# MEMORY.net
KiCad netlist of a schematic drawn in Altium Designer
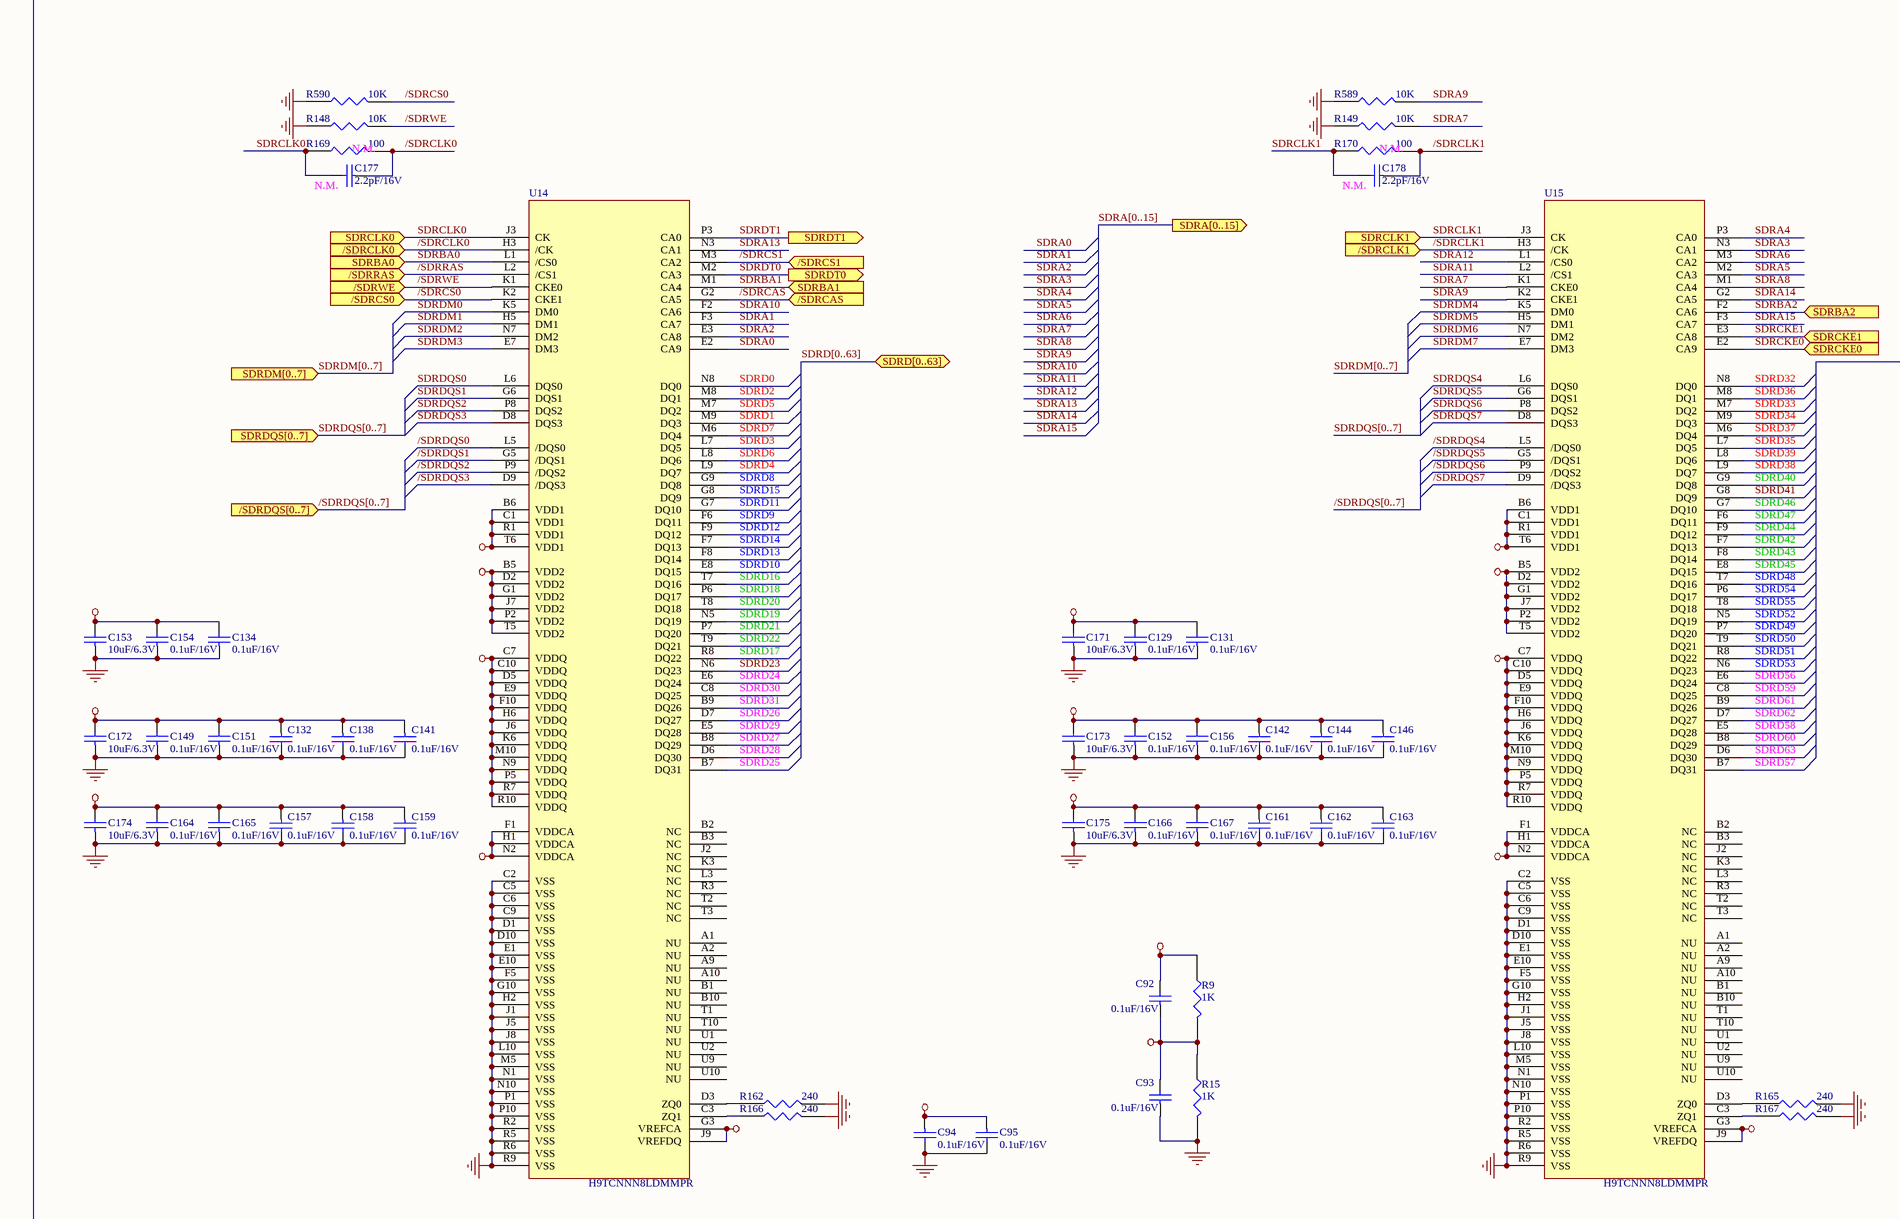
[diagram p0: MEMORY.schdoc, top left]
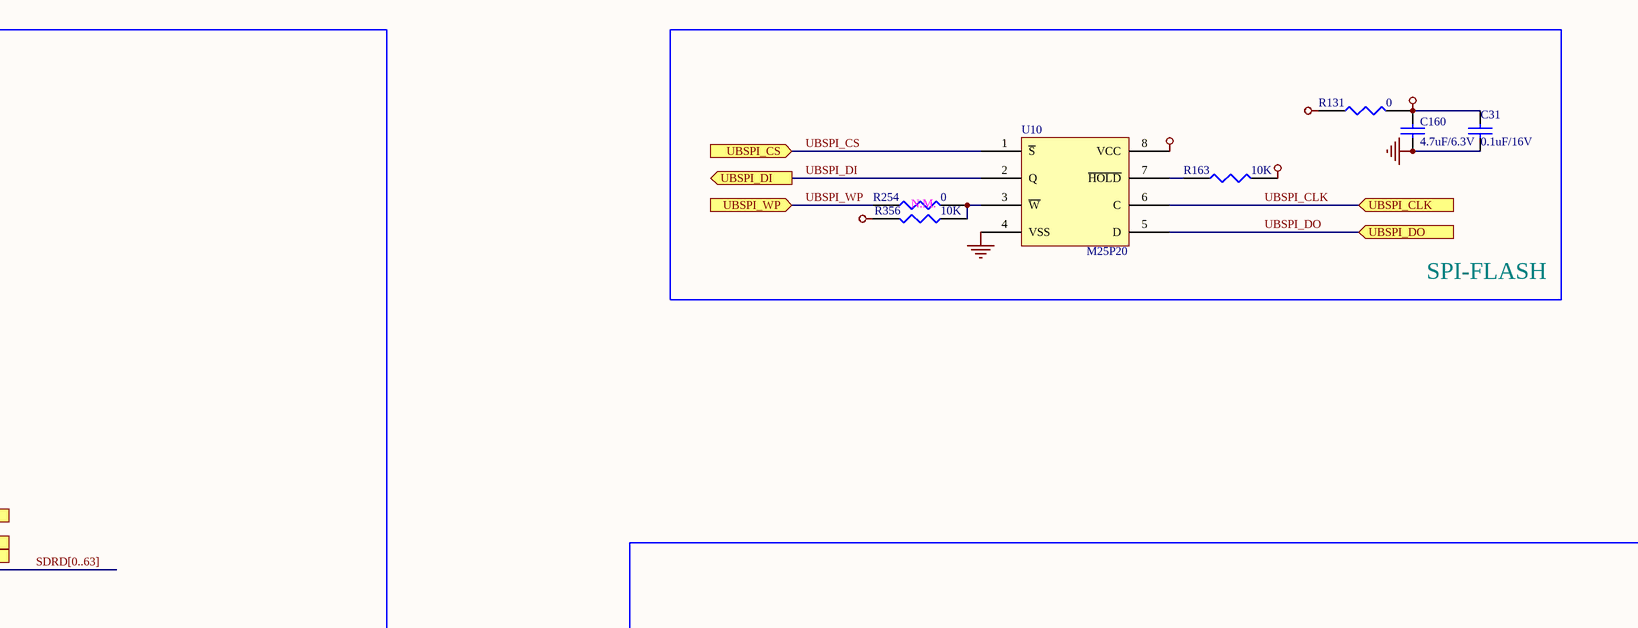
[diagram p1: MEMORY.schdoc, top right]
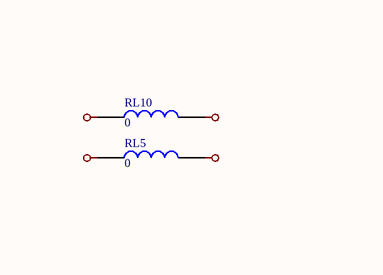
[diagram p2: MEMORY.schdoc, bottom left]
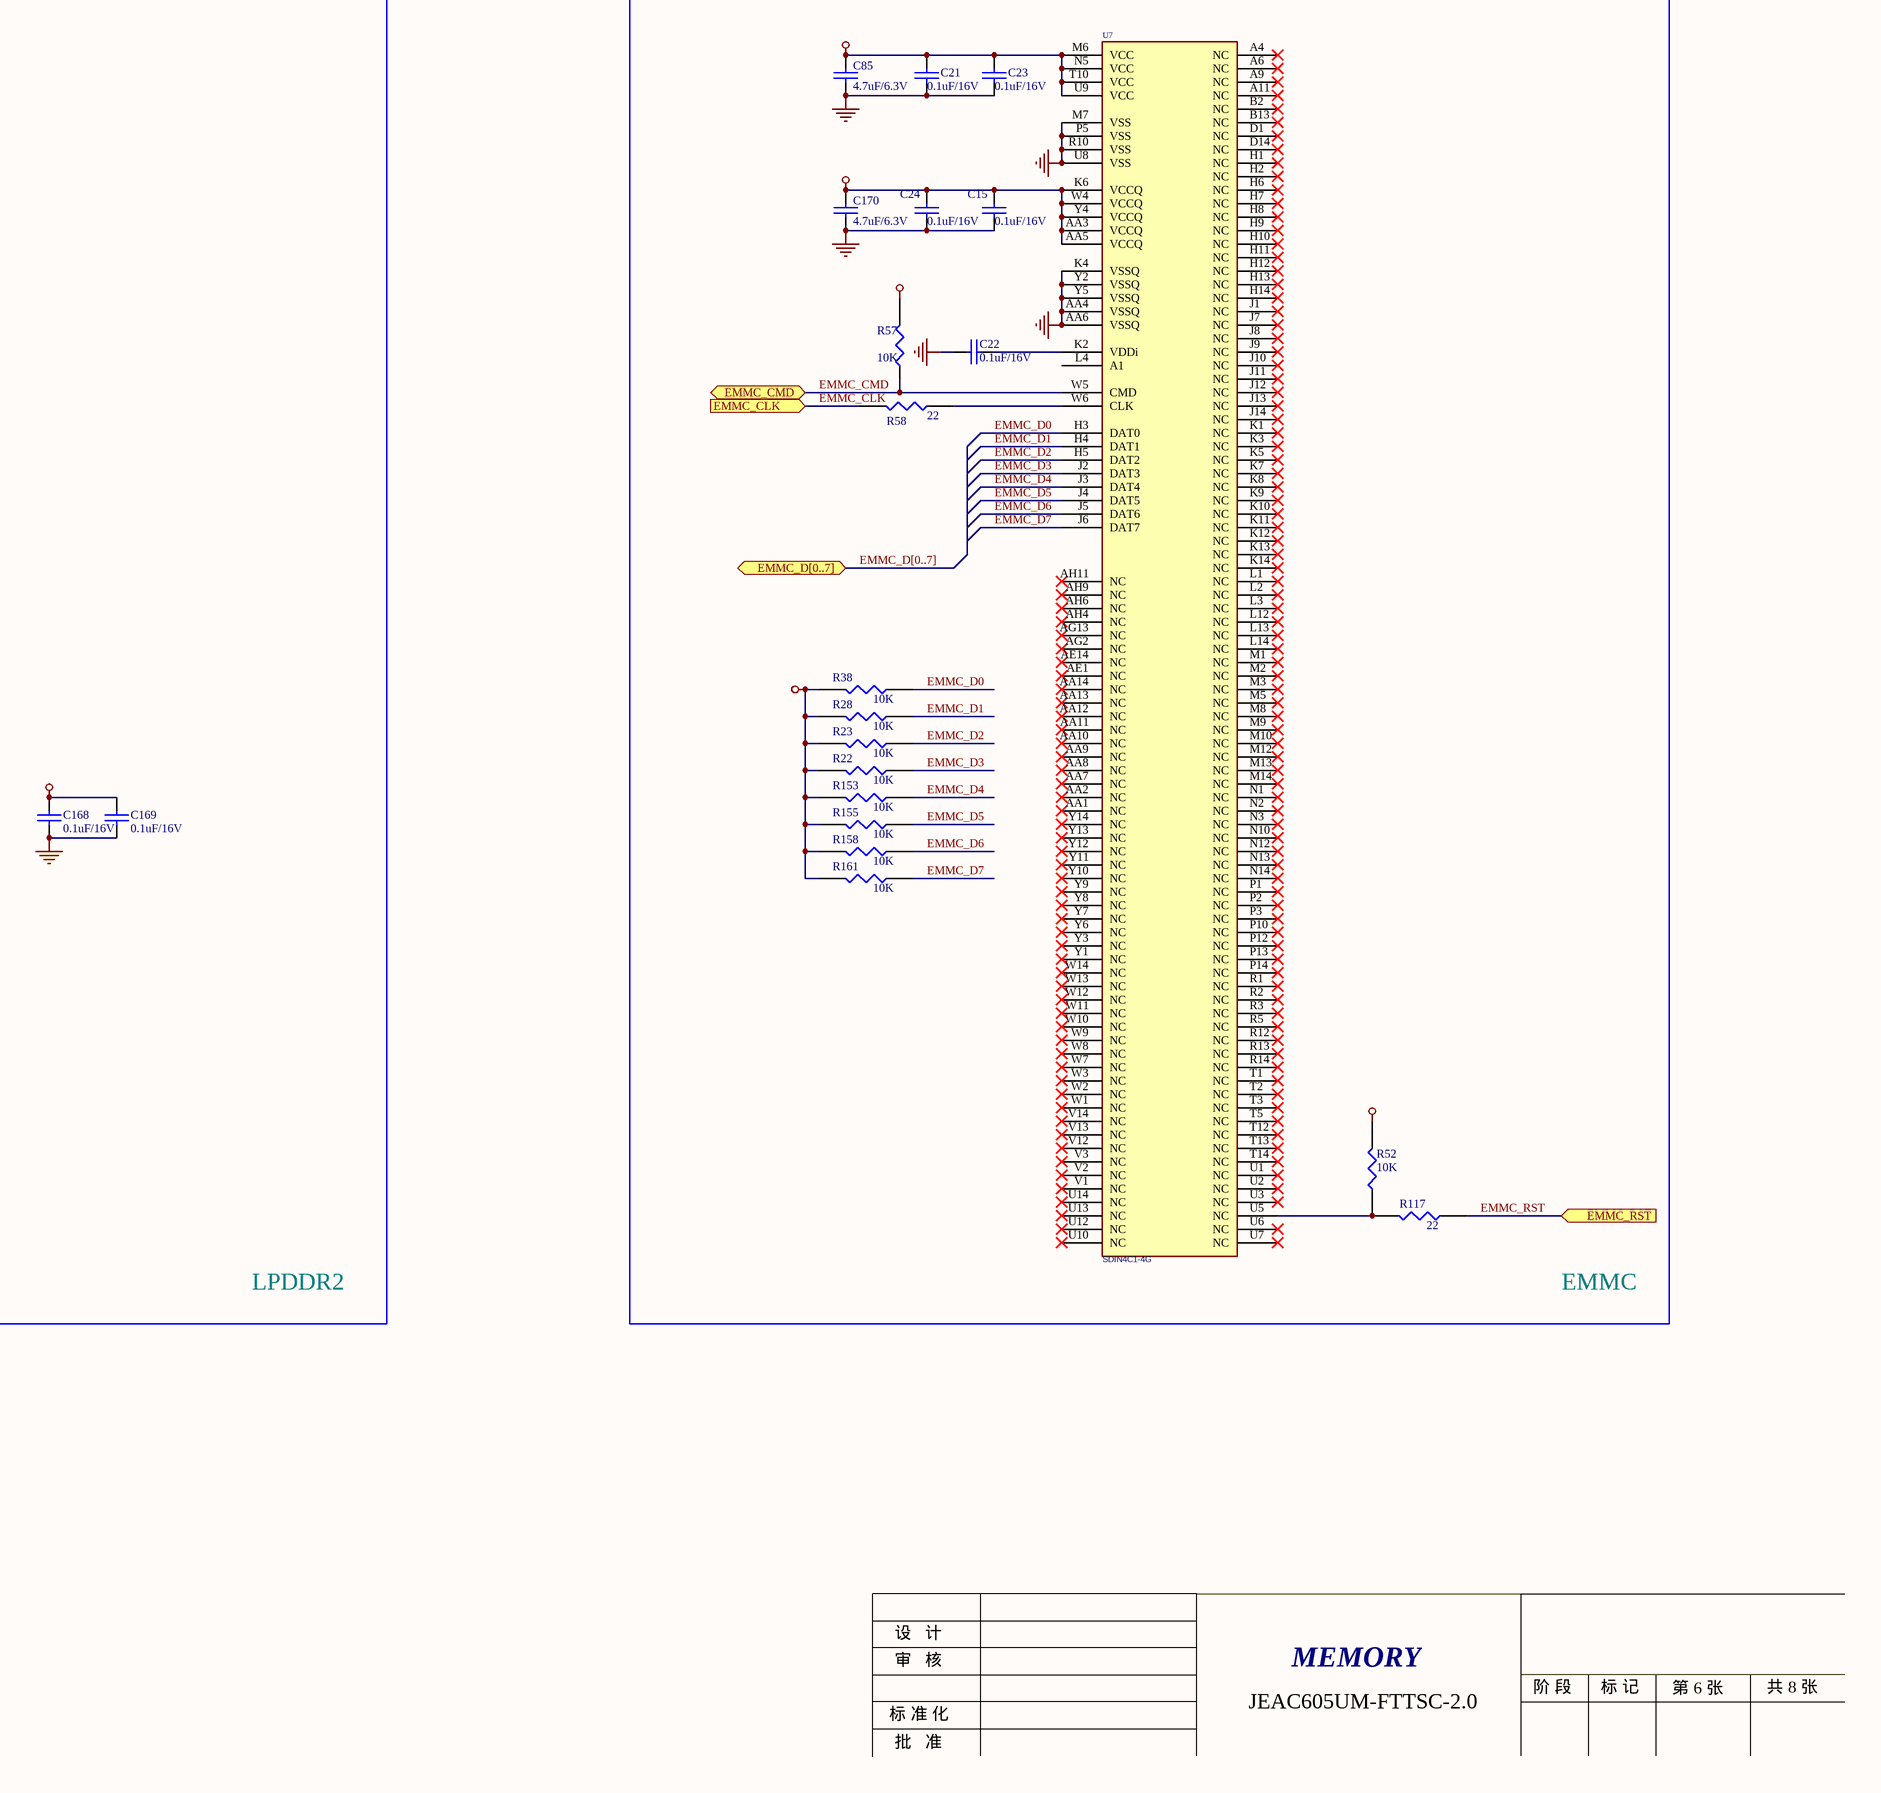
[diagram p3: MEMORY.schdoc, bottom right]

(export (version "E")
  (design (tool "Eeschema 10.0.6"))
  (components
    (comp (ref "C15")
      (value "0.1uF/16V")
      (footprint "C0402")
      (description "Capacitor")
      (libsource (lib "*") (part "CAP"))
    )
    (comp (ref "C21")
      (value "0.1uF/16V")
      (footprint "C0402")
      (description "Capacitor")
      (libsource (lib "*") (part "CAP"))
    )
    (comp (ref "C22")
      (value "0.1uF/16V")
      (footprint "C0402")
      (description "Capacitor")
      (libsource (lib "*") (part "CAP"))
    )
    (comp (ref "C23")
      (value "0.1uF/16V")
      (footprint "C0402")
      (description "Capacitor")
      (libsource (lib "*") (part "CAP"))
    )
    (comp (ref "C24")
      (value "0.1uF/16V")
      (footprint "C0402")
      (description "Capacitor")
      (libsource (lib "*") (part "CAP"))
    )
    (comp (ref "C31")
      (value "0.1uF/16V")
      (footprint "C0402")
      (description "Capacitor")
      (libsource (lib "*") (part "CAP"))
    )
    (comp (ref "C85")
      (value "4.7uF/6.3V")
      (footprint "C0603")
      (description "Capacitor")
      (libsource (lib "*") (part "CAP"))
    )
    (comp (ref "C92")
      (value "0.1uF/16V")
      (footprint "C0402")
      (description "Capacitor")
      (libsource (lib "*") (part "CAP"))
    )
    (comp (ref "C93")
      (value "0.1uF/16V")
      (footprint "C0402")
      (description "Capacitor")
      (libsource (lib "*") (part "CAP"))
    )
    (comp (ref "C94")
      (value "0.1uF/16V")
      (footprint "C0402")
      (description "Capacitor")
      (libsource (lib "*") (part "CAP"))
    )
    (comp (ref "C95")
      (value "0.1uF/16V")
      (footprint "C0402")
      (description "Capacitor")
      (libsource (lib "*") (part "CAP"))
    )
    (comp (ref "C129")
      (value "0.1uF/16V")
      (footprint "C0402")
      (description "Capacitor")
      (libsource (lib "*") (part "CAP"))
    )
    (comp (ref "C131")
      (value "0.1uF/16V")
      (footprint "C0402")
      (description "Capacitor")
      (libsource (lib "*") (part "CAP"))
    )
    (comp (ref "C132")
      (value "0.1uF/16V")
      (footprint "C0402")
      (description "Capacitor")
      (libsource (lib "*") (part "CAP"))
    )
    (comp (ref "C134")
      (value "0.1uF/16V")
      (footprint "C0402")
      (description "Capacitor")
      (libsource (lib "*") (part "CAP"))
    )
    (comp (ref "C138")
      (value "0.1uF/16V")
      (footprint "C0402")
      (description "Capacitor")
      (libsource (lib "*") (part "CAP"))
    )
    (comp (ref "C141")
      (value "0.1uF/16V")
      (footprint "C0402")
      (description "Capacitor")
      (libsource (lib "*") (part "CAP"))
    )
    (comp (ref "C142")
      (value "0.1uF/16V")
      (footprint "C0402")
      (description "Capacitor")
      (libsource (lib "*") (part "CAP"))
    )
    (comp (ref "C144")
      (value "0.1uF/16V")
      (footprint "C0402")
      (description "Capacitor")
      (libsource (lib "*") (part "CAP"))
    )
    (comp (ref "C146")
      (value "0.1uF/16V")
      (footprint "C0402")
      (description "Capacitor")
      (libsource (lib "*") (part "CAP"))
    )
    (comp (ref "C149")
      (value "0.1uF/16V")
      (footprint "C0402")
      (description "Capacitor")
      (libsource (lib "*") (part "CAP"))
    )
    (comp (ref "C151")
      (value "0.1uF/16V")
      (footprint "C0402")
      (description "Capacitor")
      (libsource (lib "*") (part "CAP"))
    )
    (comp (ref "C152")
      (value "0.1uF/16V")
      (footprint "C0402")
      (description "Capacitor")
      (libsource (lib "*") (part "CAP"))
    )
    (comp (ref "C153")
      (value "10uF/6.3V")
      (footprint "C0603")
      (description "Capacitor")
      (libsource (lib "*") (part "CAP"))
    )
    (comp (ref "C154")
      (value "0.1uF/16V")
      (footprint "C0402")
      (description "Capacitor")
      (libsource (lib "*") (part "CAP"))
    )
    (comp (ref "C156")
      (value "0.1uF/16V")
      (footprint "C0402")
      (description "Capacitor")
      (libsource (lib "*") (part "CAP"))
    )
    (comp (ref "C157")
      (value "0.1uF/16V")
      (footprint "C0402")
      (description "Capacitor")
      (libsource (lib "*") (part "CAP"))
    )
    (comp (ref "C158")
      (value "0.1uF/16V")
      (footprint "C0402")
      (description "Capacitor")
      (libsource (lib "*") (part "CAP"))
    )
    (comp (ref "C159")
      (value "0.1uF/16V")
      (footprint "C0402")
      (description "Capacitor")
      (libsource (lib "*") (part "CAP"))
    )
    (comp (ref "C160")
      (value "4.7uF/6.3V")
      (footprint "C0603")
      (description "Capacitor")
      (libsource (lib "*") (part "CAP"))
    )
    (comp (ref "C161")
      (value "0.1uF/16V")
      (footprint "C0402")
      (description "Capacitor")
      (libsource (lib "*") (part "CAP"))
    )
    (comp (ref "C162")
      (value "0.1uF/16V")
      (footprint "C0402")
      (description "Capacitor")
      (libsource (lib "*") (part "CAP"))
    )
    (comp (ref "C163")
      (value "0.1uF/16V")
      (footprint "C0402")
      (description "Capacitor")
      (libsource (lib "*") (part "CAP"))
    )
    (comp (ref "C164")
      (value "0.1uF/16V")
      (footprint "C0402")
      (description "Capacitor")
      (libsource (lib "*") (part "CAP"))
    )
    (comp (ref "C165")
      (value "0.1uF/16V")
      (footprint "C0402")
      (description "Capacitor")
      (libsource (lib "*") (part "CAP"))
    )
    (comp (ref "C166")
      (value "0.1uF/16V")
      (footprint "C0402")
      (description "Capacitor")
      (libsource (lib "*") (part "CAP"))
    )
    (comp (ref "C167")
      (value "0.1uF/16V")
      (footprint "C0402")
      (description "Capacitor")
      (libsource (lib "*") (part "CAP"))
    )
    (comp (ref "C168")
      (value "0.1uF/16V")
      (footprint "C0402")
      (description "Capacitor")
      (libsource (lib "*") (part "CAP"))
    )
    (comp (ref "C169")
      (value "0.1uF/16V")
      (footprint "C0402")
      (description "Capacitor")
      (libsource (lib "*") (part "CAP"))
    )
    (comp (ref "C170")
      (value "4.7uF/6.3V")
      (footprint "C0603")
      (description "Capacitor")
      (libsource (lib "*") (part "CAP"))
    )
    (comp (ref "C171")
      (value "10uF/6.3V")
      (footprint "C0603")
      (description "Capacitor")
      (libsource (lib "*") (part "CAP"))
    )
    (comp (ref "C172")
      (value "10uF/6.3V")
      (footprint "C0603")
      (description "Capacitor")
      (libsource (lib "*") (part "CAP"))
    )
    (comp (ref "C173")
      (value "10uF/6.3V")
      (footprint "C0603")
      (description "Capacitor")
      (libsource (lib "*") (part "CAP"))
    )
    (comp (ref "C174")
      (value "10uF/6.3V")
      (footprint "C0603")
      (description "Capacitor")
      (libsource (lib "*") (part "CAP"))
    )
    (comp (ref "C175")
      (value "10uF/6.3V")
      (footprint "C0603")
      (description "Capacitor")
      (libsource (lib "*") (part "CAP"))
    )
    (comp (ref "C177")
      (value "2.2pF/16V")
      (footprint "C0402")
      (description "Capacitor")
      (libsource (lib "*") (part "CAP"))
    )
    (comp (ref "C178")
      (value "2.2pF/16V")
      (footprint "C0402")
      (description "Capacitor")
      (libsource (lib "*") (part "CAP"))
    )
    (comp (ref "R9") (value "1K") (footprint "R0402") (libsource (lib "*") (part "RES1")))
    (comp (ref "R15") (value "1K") (footprint "R0402") (libsource (lib "*") (part "RES1")))
    (comp (ref "R22") (value "10K") (footprint "R0402") (libsource (lib "*") (part "RES1")))
    (comp (ref "R23") (value "10K") (footprint "R0402") (libsource (lib "*") (part "RES1")))
    (comp (ref "R28") (value "10K") (footprint "R0402") (libsource (lib "*") (part "RES1")))
    (comp (ref "R38") (value "10K") (footprint "R0402") (libsource (lib "*") (part "RES1")))
    (comp (ref "R52") (value "10K") (footprint "R0402") (libsource (lib "*") (part "RES1")))
    (comp (ref "R57") (value "10K") (footprint "R0402") (libsource (lib "*") (part "RES1")))
    (comp (ref "R58") (value "22") (footprint "R0402") (libsource (lib "*") (part "RES1")))
    (comp (ref "R117") (value "22") (footprint "R0402") (libsource (lib "*") (part "RES1")))
    (comp (ref "R131") (value "0") (footprint "R0402") (libsource (lib "*") (part "RES1")))
    (comp (ref "R148") (value "10K") (footprint "R0402") (libsource (lib "*") (part "RES1")))
    (comp (ref "R149") (value "10K") (footprint "R0402") (libsource (lib "*") (part "RES1")))
    (comp (ref "R153") (value "10K") (footprint "R0402") (libsource (lib "*") (part "RES1")))
    (comp (ref "R155") (value "10K") (footprint "R0402") (libsource (lib "*") (part "RES1")))
    (comp (ref "R158") (value "10K") (footprint "R0402") (libsource (lib "*") (part "RES1")))
    (comp (ref "R161") (value "10K") (footprint "R0402") (libsource (lib "*") (part "RES1")))
    (comp (ref "R162") (value "240") (footprint "R0402") (libsource (lib "*") (part "RES1")))
    (comp (ref "R163") (value "10K") (footprint "R0402") (libsource (lib "*") (part "RES1")))
    (comp (ref "R165") (value "240") (footprint "R0402") (libsource (lib "*") (part "RES1")))
    (comp (ref "R166") (value "240") (footprint "R0402") (libsource (lib "*") (part "RES1")))
    (comp (ref "R167") (value "240") (footprint "R0402") (libsource (lib "*") (part "RES1")))
    (comp (ref "R169") (value "100") (footprint "R0402") (libsource (lib "*") (part "RES1")))
    (comp (ref "R170") (value "100") (footprint "R0402") (libsource (lib "*") (part "RES1")))
    (comp (ref "R254") (value "0") (footprint "R0402") (libsource (lib "*") (part "RES1")))
    (comp (ref "R356") (value "10K") (footprint "R0402") (libsource (lib "*") (part "RES1")))
    (comp (ref "R589") (value "10K") (footprint "R0402") (libsource (lib "*") (part "RES1")))
    (comp (ref "R590") (value "10K") (footprint "R0402") (libsource (lib "*") (part "RES1")))
    (comp (ref "RL5") (value "0") (footprint "L0603") (libsource (lib "*") (part "INDUCTOR")))
    (comp (ref "RL10") (value "0") (footprint "L0603") (libsource (lib "*") (part "INDUCTOR")))
    (comp (ref "U7") (value "SDIN4C1-4G") (libsource (lib "SOM3621") (part "SDIN3C2-16G")))
    (comp (ref "U10") (value "M25P20") (footprint "U-SO-8-1_27") (libsource (lib "*") (part "A25L80P")))
    (comp (ref "U14")
      (value "H9TCNNN8LDMMPR")
      (footprint "U-FBGA-134-0_65")
      (libsource (lib "*") (part "EDB8132B2MA"))
    )
    (comp (ref "U15")
      (value "H9TCNNN8LDMMPR")
      (footprint "U-FBGA-134-0_65")
      (libsource (lib "*") (part "EDB8132B2MA"))
    )
  )
  (nets
    (net (code "9") (name "/EMMC_CLK") (class "Default")
      (node (ref "R58") (pin "2") (pinfunction "2_2") (pintype "passive"))
    )
    (net (code "10") (name "/EMMC_CMD") (class "Default")
      (node (ref "R57") (pin "1") (pinfunction "1_1") (pintype "passive"))
      (node (ref "U7") (pin "W5") (pinfunction "CMD_W5") (pintype "passive"))
    )
    (net (code "11") (name "/EMMC_D0") (class "Default")
      (node (ref "R38") (pin "1") (pinfunction "1_1") (pintype "passive"))
      (node (ref "U7") (pin "H3") (pinfunction "DAT0_H3") (pintype "passive"))
    )
    (net (code "12") (name "/EMMC_D1") (class "Default")
      (node (ref "R28") (pin "1") (pinfunction "1_1") (pintype "passive"))
      (node (ref "U7") (pin "H4") (pinfunction "DAT1_H4") (pintype "passive"))
    )
    (net (code "13") (name "/EMMC_D2") (class "Default")
      (node (ref "R23") (pin "1") (pinfunction "1_1") (pintype "passive"))
      (node (ref "U7") (pin "H5") (pinfunction "DAT2_H5") (pintype "passive"))
    )
    (net (code "14") (name "/EMMC_D3") (class "Default")
      (node (ref "R22") (pin "1") (pinfunction "1_1") (pintype "passive"))
      (node (ref "U7") (pin "J2") (pinfunction "DAT3_J2") (pintype "passive"))
    )
    (net (code "15") (name "/EMMC_D4") (class "Default")
      (node (ref "R153") (pin "1") (pinfunction "1_1") (pintype "passive"))
      (node (ref "U7") (pin "J3") (pinfunction "DAT4_J3") (pintype "passive"))
    )
    (net (code "16") (name "/EMMC_D5") (class "Default")
      (node (ref "R155") (pin "1") (pinfunction "1_1") (pintype "passive"))
      (node (ref "U7") (pin "J4") (pinfunction "DAT5_J4") (pintype "passive"))
    )
    (net (code "17") (name "/EMMC_D6") (class "Default")
      (node (ref "R158") (pin "1") (pinfunction "1_1") (pintype "passive"))
      (node (ref "U7") (pin "J5") (pinfunction "DAT6_J5") (pintype "passive"))
    )
    (net (code "18") (name "/EMMC_D7") (class "Default")
      (node (ref "R161") (pin "1") (pinfunction "1_1") (pintype "passive"))
      (node (ref "U7") (pin "J6") (pinfunction "DAT7_J6") (pintype "passive"))
    )
    (net (code "20") (name "/EMMC_RST") (class "Default")
      (node (ref "R117") (pin "1") (pinfunction "1_1") (pintype "passive"))
    )
    (net (code "21") (name "/SDRA0") (class "Default")
      (node (ref "U14") (pin "E2") (pinfunction "CA9_E2") (pintype "passive"))
    )
    (net (code "22") (name "/SDRA1") (class "Default")
      (node (ref "U14") (pin "F3") (pinfunction "CA7_F3") (pintype "passive"))
    )
    (net (code "23") (name "/SDRA2") (class "Default")
      (node (ref "U14") (pin "E3") (pinfunction "CA8_E3") (pintype "passive"))
    )
    (net (code "24") (name "/SDRA3") (class "Default")
      (node (ref "U15") (pin "N3") (pinfunction "CA1_N3") (pintype "passive"))
    )
    (net (code "25") (name "/SDRA4") (class "Default")
      (node (ref "U15") (pin "P3") (pinfunction "CA0_P3") (pintype "passive"))
    )
    (net (code "26") (name "/SDRA5") (class "Default")
      (node (ref "U15") (pin "M2") (pinfunction "CA3_M2") (pintype "passive"))
    )
    (net (code "27") (name "/SDRA6") (class "Default")
      (node (ref "U15") (pin "M3") (pinfunction "CA2_M3") (pintype "passive"))
    )
    (net (code "28") (name "/SDRA7") (class "Default")
      (node (ref "R149") (pin "2") (pinfunction "2_2") (pintype "passive"))
      (node (ref "U15") (pin "K1") (pinfunction "CKE0_K1") (pintype "passive"))
    )
    (net (code "29") (name "/SDRA8") (class "Default")
      (node (ref "U15") (pin "M1") (pinfunction "CA4_M1") (pintype "passive"))
    )
    (net (code "30") (name "/SDRA9") (class "Default")
      (node (ref "R589") (pin "2") (pinfunction "2_2") (pintype "passive"))
      (node (ref "U15") (pin "K2") (pinfunction "CKE1_K2") (pintype "passive"))
    )
    (net (code "31") (name "/SDRA10") (class "Default")
      (node (ref "U14") (pin "F2") (pinfunction "CA6_F2") (pintype "passive"))
    )
    (net (code "32") (name "/SDRA11") (class "Default")
      (node (ref "U15") (pin "L2") (pinfunction "/CS1_L2") (pintype "passive"))
    )
    (net (code "33") (name "/SDRA12") (class "Default")
      (node (ref "U15") (pin "L1") (pinfunction "/CS0_L1") (pintype "passive"))
    )
    (net (code "34") (name "/SDRA13") (class "Default")
      (node (ref "U14") (pin "N3") (pinfunction "CA1_N3") (pintype "passive"))
    )
    (net (code "35") (name "/SDRA14") (class "Default")
      (node (ref "U15") (pin "G2") (pinfunction "CA5_G2") (pintype "passive"))
    )
    (net (code "36") (name "/SDRA15") (class "Default")
      (node (ref "U15") (pin "F3") (pinfunction "CA7_F3") (pintype "passive"))
    )
    (net (code "38") (name "/SDRBA0") (class "Default")
      (node (ref "U14") (pin "L1") (pinfunction "/CS0_L1") (pintype "passive"))
    )
    (net (code "39") (name "/SDRBA1") (class "Default")
      (node (ref "U14") (pin "M1") (pinfunction "CA4_M1") (pintype "passive"))
    )
    (net (code "40") (name "/SDRBA2") (class "Default")
      (node (ref "U15") (pin "F2") (pinfunction "CA6_F2") (pintype "passive"))
    )
    (net (code "41") (name "/SDRCKE0") (class "Default")
      (node (ref "U15") (pin "E2") (pinfunction "CA9_E2") (pintype "passive"))
    )
    (net (code "42") (name "/SDRCKE1") (class "Default")
      (node (ref "U15") (pin "E3") (pinfunction "CA8_E3") (pintype "passive"))
    )
    (net (code "43") (name "/SDRCLK0") (class "Default")
      (node (ref "C177") (pin "2") (pinfunction "2_2") (pintype "passive"))
      (node (ref "R169") (pin "1") (pinfunction "1_1") (pintype "passive"))
      (node (ref "U14") (pin "J3") (pinfunction "CK_J3") (pintype "passive"))
    )
    (net (code "44") (name "/SDRCLK1") (class "Default")
      (node (ref "C178") (pin "2") (pinfunction "2_2") (pintype "passive"))
      (node (ref "R170") (pin "1") (pinfunction "1_1") (pintype "passive"))
      (node (ref "U15") (pin "J3") (pinfunction "CK_J3") (pintype "passive"))
    )
    (net (code "45") (name "/SDRD0") (class "Default")
      (node (ref "U14") (pin "N8") (pinfunction "DQ0_N8") (pintype "passive"))
    )
    (net (code "46") (name "/SDRD1") (class "Default")
      (node (ref "U14") (pin "M9") (pinfunction "DQ3_M9") (pintype "passive"))
    )
    (net (code "47") (name "/SDRD2") (class "Default")
      (node (ref "U14") (pin "M8") (pinfunction "DQ1_M8") (pintype "passive"))
    )
    (net (code "48") (name "/SDRD3") (class "Default")
      (node (ref "U14") (pin "L7") (pinfunction "DQ5_L7") (pintype "passive"))
    )
    (net (code "49") (name "/SDRD4") (class "Default")
      (node (ref "U14") (pin "L9") (pinfunction "DQ7_L9") (pintype "passive"))
    )
    (net (code "50") (name "/SDRD5") (class "Default")
      (node (ref "U14") (pin "M7") (pinfunction "DQ2_M7") (pintype "passive"))
    )
    (net (code "51") (name "/SDRD6") (class "Default")
      (node (ref "U14") (pin "L8") (pinfunction "DQ6_L8") (pintype "passive"))
    )
    (net (code "52") (name "/SDRD7") (class "Default")
      (node (ref "U14") (pin "M6") (pinfunction "DQ4_M6") (pintype "passive"))
    )
    (net (code "53") (name "/SDRD8") (class "Default")
      (node (ref "U14") (pin "G9") (pinfunction "DQ8_G9") (pintype "passive"))
    )
    (net (code "54") (name "/SDRD9") (class "Default")
      (node (ref "U14") (pin "F6") (pinfunction "DQ11_F6") (pintype "passive"))
    )
    (net (code "55") (name "/SDRD10") (class "Default")
      (node (ref "U14") (pin "E8") (pinfunction "DQ15_E8") (pintype "passive"))
    )
    (net (code "56") (name "/SDRD11") (class "Default")
      (node (ref "U14") (pin "G7") (pinfunction "DQ10_G7") (pintype "passive"))
    )
    (net (code "57") (name "/SDRD12") (class "Default")
      (node (ref "U14") (pin "F9") (pinfunction "DQ12_F9") (pintype "passive"))
    )
    (net (code "58") (name "/SDRD13") (class "Default")
      (node (ref "U14") (pin "F8") (pinfunction "DQ14_F8") (pintype "passive"))
    )
    (net (code "59") (name "/SDRD14") (class "Default")
      (node (ref "U14") (pin "F7") (pinfunction "DQ13_F7") (pintype "passive"))
    )
    (net (code "60") (name "/SDRD15") (class "Default")
      (node (ref "U14") (pin "G8") (pinfunction "DQ9_G8") (pintype "passive"))
    )
    (net (code "61") (name "/SDRD16") (class "Default")
      (node (ref "U14") (pin "T7") (pinfunction "DQ16_T7") (pintype "passive"))
    )
    (net (code "62") (name "/SDRD17") (class "Default")
      (node (ref "U14") (pin "R8") (pinfunction "DQ22_R8") (pintype "passive"))
    )
    (net (code "63") (name "/SDRD18") (class "Default")
      (node (ref "U14") (pin "P6") (pinfunction "DQ17_P6") (pintype "passive"))
    )
    (net (code "64") (name "/SDRD19") (class "Default")
      (node (ref "U14") (pin "N5") (pinfunction "DQ19_N5") (pintype "passive"))
    )
    (net (code "65") (name "/SDRD20") (class "Default")
      (node (ref "U14") (pin "T8") (pinfunction "DQ18_T8") (pintype "passive"))
    )
    (net (code "66") (name "/SDRD21") (class "Default")
      (node (ref "U14") (pin "P7") (pinfunction "DQ20_P7") (pintype "passive"))
    )
    (net (code "67") (name "/SDRD22") (class "Default")
      (node (ref "U14") (pin "T9") (pinfunction "DQ21_T9") (pintype "passive"))
    )
    (net (code "68") (name "/SDRD23") (class "Default")
      (node (ref "U14") (pin "N6") (pinfunction "DQ23_N6") (pintype "passive"))
    )
    (net (code "69") (name "/SDRD24") (class "Default")
      (node (ref "U14") (pin "E6") (pinfunction "DQ24_E6") (pintype "passive"))
    )
    (net (code "70") (name "/SDRD25") (class "Default")
      (node (ref "U14") (pin "B7") (pinfunction "DQ31_B7") (pintype "passive"))
    )
    (net (code "71") (name "/SDRD26") (class "Default")
      (node (ref "U14") (pin "D7") (pinfunction "DQ27_D7") (pintype "passive"))
    )
    (net (code "72") (name "/SDRD27") (class "Default")
      (node (ref "U14") (pin "B8") (pinfunction "DQ29_B8") (pintype "passive"))
    )
    (net (code "73") (name "/SDRD28") (class "Default")
      (node (ref "U14") (pin "D6") (pinfunction "DQ30_D6") (pintype "passive"))
    )
    (net (code "74") (name "/SDRD29") (class "Default")
      (node (ref "U14") (pin "E5") (pinfunction "DQ28_E5") (pintype "passive"))
    )
    (net (code "75") (name "/SDRD30") (class "Default")
      (node (ref "U14") (pin "C8") (pinfunction "DQ25_C8") (pintype "passive"))
    )
    (net (code "76") (name "/SDRD31") (class "Default")
      (node (ref "U14") (pin "B9") (pinfunction "DQ26_B9") (pintype "passive"))
    )
    (net (code "77") (name "/SDRD32") (class "Default")
      (node (ref "U15") (pin "N8") (pinfunction "DQ0_N8") (pintype "passive"))
    )
    (net (code "78") (name "/SDRD33") (class "Default")
      (node (ref "U15") (pin "M7") (pinfunction "DQ2_M7") (pintype "passive"))
    )
    (net (code "79") (name "/SDRD34") (class "Default")
      (node (ref "U15") (pin "M9") (pinfunction "DQ3_M9") (pintype "passive"))
    )
    (net (code "80") (name "/SDRD35") (class "Default")
      (node (ref "U15") (pin "L7") (pinfunction "DQ5_L7") (pintype "passive"))
    )
    (net (code "81") (name "/SDRD36") (class "Default")
      (node (ref "U15") (pin "M8") (pinfunction "DQ1_M8") (pintype "passive"))
    )
    (net (code "82") (name "/SDRD37") (class "Default")
      (node (ref "U15") (pin "M6") (pinfunction "DQ4_M6") (pintype "passive"))
    )
    (net (code "83") (name "/SDRD38") (class "Default")
      (node (ref "U15") (pin "L9") (pinfunction "DQ7_L9") (pintype "passive"))
    )
    (net (code "84") (name "/SDRD39") (class "Default")
      (node (ref "U15") (pin "L8") (pinfunction "DQ6_L8") (pintype "passive"))
    )
    (net (code "85") (name "/SDRD40") (class "Default")
      (node (ref "U15") (pin "G9") (pinfunction "DQ8_G9") (pintype "passive"))
    )
    (net (code "86") (name "/SDRD41") (class "Default")
      (node (ref "U15") (pin "G8") (pinfunction "DQ9_G8") (pintype "passive"))
    )
    (net (code "87") (name "/SDRD42") (class "Default")
      (node (ref "U15") (pin "F7") (pinfunction "DQ13_F7") (pintype "passive"))
    )
    (net (code "88") (name "/SDRD43") (class "Default")
      (node (ref "U15") (pin "F8") (pinfunction "DQ14_F8") (pintype "passive"))
    )
    (net (code "89") (name "/SDRD44") (class "Default")
      (node (ref "U15") (pin "F9") (pinfunction "DQ12_F9") (pintype "passive"))
    )
    (net (code "90") (name "/SDRD45") (class "Default")
      (node (ref "U15") (pin "E8") (pinfunction "DQ15_E8") (pintype "passive"))
    )
    (net (code "91") (name "/SDRD46") (class "Default")
      (node (ref "U15") (pin "G7") (pinfunction "DQ10_G7") (pintype "passive"))
    )
    (net (code "92") (name "/SDRD47") (class "Default")
      (node (ref "U15") (pin "F6") (pinfunction "DQ11_F6") (pintype "passive"))
    )
    (net (code "93") (name "/SDRD48") (class "Default")
      (node (ref "U15") (pin "T7") (pinfunction "DQ16_T7") (pintype "passive"))
    )
    (net (code "94") (name "/SDRD49") (class "Default")
      (node (ref "U15") (pin "P7") (pinfunction "DQ20_P7") (pintype "passive"))
    )
    (net (code "95") (name "/SDRD50") (class "Default")
      (node (ref "U15") (pin "T9") (pinfunction "DQ21_T9") (pintype "passive"))
    )
    (net (code "96") (name "/SDRD51") (class "Default")
      (node (ref "U15") (pin "R8") (pinfunction "DQ22_R8") (pintype "passive"))
    )
    (net (code "97") (name "/SDRD52") (class "Default")
      (node (ref "U15") (pin "N5") (pinfunction "DQ19_N5") (pintype "passive"))
    )
    (net (code "98") (name "/SDRD53") (class "Default")
      (node (ref "U15") (pin "N6") (pinfunction "DQ23_N6") (pintype "passive"))
    )
    (net (code "99") (name "/SDRD54") (class "Default")
      (node (ref "U15") (pin "P6") (pinfunction "DQ17_P6") (pintype "passive"))
    )
    (net (code "100") (name "/SDRD55") (class "Default")
      (node (ref "U15") (pin "T8") (pinfunction "DQ18_T8") (pintype "passive"))
    )
    (net (code "101") (name "/SDRD56") (class "Default")
      (node (ref "U15") (pin "E6") (pinfunction "DQ24_E6") (pintype "passive"))
    )
    (net (code "102") (name "/SDRD57") (class "Default")
      (node (ref "U15") (pin "B7") (pinfunction "DQ31_B7") (pintype "passive"))
    )
    (net (code "103") (name "/SDRD58") (class "Default")
      (node (ref "U15") (pin "E5") (pinfunction "DQ28_E5") (pintype "passive"))
    )
    (net (code "104") (name "/SDRD59") (class "Default")
      (node (ref "U15") (pin "C8") (pinfunction "DQ25_C8") (pintype "passive"))
    )
    (net (code "105") (name "/SDRD60") (class "Default")
      (node (ref "U15") (pin "B8") (pinfunction "DQ29_B8") (pintype "passive"))
    )
    (net (code "106") (name "/SDRD61") (class "Default")
      (node (ref "U15") (pin "B9") (pinfunction "DQ26_B9") (pintype "passive"))
    )
    (net (code "107") (name "/SDRD62") (class "Default")
      (node (ref "U15") (pin "D7") (pinfunction "DQ27_D7") (pintype "passive"))
    )
    (net (code "108") (name "/SDRD63") (class "Default")
      (node (ref "U15") (pin "D6") (pinfunction "DQ30_D6") (pintype "passive"))
    )
    (net (code "109") (name "/SDRDM0") (class "Default")
      (node (ref "U14") (pin "K5") (pinfunction "DM0_K5") (pintype "passive"))
    )
    (net (code "110") (name "/SDRDM1") (class "Default")
      (node (ref "U14") (pin "H5") (pinfunction "DM1_H5") (pintype "passive"))
    )
    (net (code "111") (name "/SDRDM2") (class "Default")
      (node (ref "U14") (pin "N7") (pinfunction "DM2_N7") (pintype "passive"))
    )
    (net (code "112") (name "/SDRDM3") (class "Default")
      (node (ref "U14") (pin "E7") (pinfunction "DM3_E7") (pintype "passive"))
    )
    (net (code "113") (name "/SDRDM4") (class "Default")
      (node (ref "U15") (pin "K5") (pinfunction "DM0_K5") (pintype "passive"))
    )
    (net (code "114") (name "/SDRDM5") (class "Default")
      (node (ref "U15") (pin "H5") (pinfunction "DM1_H5") (pintype "passive"))
    )
    (net (code "115") (name "/SDRDM6") (class "Default")
      (node (ref "U15") (pin "N7") (pinfunction "DM2_N7") (pintype "passive"))
    )
    (net (code "116") (name "/SDRDM7") (class "Default")
      (node (ref "U15") (pin "E7") (pinfunction "DM3_E7") (pintype "passive"))
    )
    (net (code "118") (name "/SDRDQS0") (class "Default")
      (node (ref "U14") (pin "L6") (pinfunction "DQS0_L6") (pintype "passive"))
    )
    (net (code "119") (name "/SDRDQS1") (class "Default")
      (node (ref "U14") (pin "G6") (pinfunction "DQS1_G6") (pintype "passive"))
    )
    (net (code "120") (name "/SDRDQS2") (class "Default")
      (node (ref "U14") (pin "P8") (pinfunction "DQS2_P8") (pintype "passive"))
    )
    (net (code "121") (name "/SDRDQS3") (class "Default")
      (node (ref "U14") (pin "D8") (pinfunction "DQS3_D8") (pintype "passive"))
    )
    (net (code "122") (name "/SDRDQS4") (class "Default")
      (node (ref "U15") (pin "L6") (pinfunction "DQS0_L6") (pintype "passive"))
    )
    (net (code "123") (name "/SDRDQS5") (class "Default")
      (node (ref "U15") (pin "G6") (pinfunction "DQS1_G6") (pintype "passive"))
    )
    (net (code "124") (name "/SDRDQS6") (class "Default")
      (node (ref "U15") (pin "P8") (pinfunction "DQS2_P8") (pintype "passive"))
    )
    (net (code "125") (name "/SDRDQS7") (class "Default")
      (node (ref "U15") (pin "D8") (pinfunction "DQS3_D8") (pintype "passive"))
    )
    (net (code "127") (name "/SDRDT0") (class "Default")
      (node (ref "U14") (pin "M2") (pinfunction "CA3_M2") (pintype "passive"))
    )
    (net (code "128") (name "/SDRDT1") (class "Default")
      (node (ref "U14") (pin "P3") (pinfunction "CA0_P3") (pintype "passive"))
    )
    (net (code "130") (name "/UBSPI_CLK") (class "Default")
      (node (ref "U10") (pin "6") (pinfunction "C_6") (pintype "passive"))
    )
    (net (code "131") (name "/UBSPI_CS") (class "Default")
      (node (ref "U10") (pin "1") (pinfunction "~{S}_1") (pintype "passive"))
    )
    (net (code "132") (name "/UBSPI_DI") (class "Default")
      (node (ref "U10") (pin "2") (pinfunction "Q_2") (pintype "passive"))
    )
    (net (code "133") (name "/UBSPI_DO") (class "Default")
      (node (ref "U10") (pin "5") (pinfunction "D_5") (pintype "passive"))
    )
    (net (code "134") (name "/UBSPI_WP") (class "Default")
      (node (ref "R254") (pin "1") (pinfunction "1_1") (pintype "passive"))
    )
    (net (code "135") (name "/{slash}SDRCAS") (class "Default")
      (node (ref "U14") (pin "G2") (pinfunction "CA5_G2") (pintype "passive"))
    )
    (net (code "136") (name "/{slash}SDRCLK0") (class "Default")
      (node (ref "C177") (pin "1") (pinfunction "1_1") (pintype "passive"))
      (node (ref "R169") (pin "2") (pinfunction "2_2") (pintype "passive"))
      (node (ref "U14") (pin "H3") (pinfunction "/CK_H3") (pintype "passive"))
    )
    (net (code "137") (name "/{slash}SDRCLK1") (class "Default")
      (node (ref "C178") (pin "1") (pinfunction "1_1") (pintype "passive"))
      (node (ref "R170") (pin "2") (pinfunction "2_2") (pintype "passive"))
      (node (ref "U15") (pin "H3") (pinfunction "/CK_H3") (pintype "passive"))
    )
    (net (code "138") (name "/{slash}SDRCS0") (class "Default")
      (node (ref "R590") (pin "2") (pinfunction "2_2") (pintype "passive"))
      (node (ref "U14") (pin "K2") (pinfunction "CKE1_K2") (pintype "passive"))
    )
    (net (code "139") (name "/{slash}SDRCS1") (class "Default")
      (node (ref "U14") (pin "M3") (pinfunction "CA2_M3") (pintype "passive"))
    )
    (net (code "140") (name "/{slash}SDRDQS0") (class "Default")
      (node (ref "U14") (pin "L5") (pinfunction "/DQS0_L5") (pintype "passive"))
    )
    (net (code "141") (name "/{slash}SDRDQS1") (class "Default")
      (node (ref "U14") (pin "G5") (pinfunction "/DQS1_G5") (pintype "passive"))
    )
    (net (code "142") (name "/{slash}SDRDQS2") (class "Default")
      (node (ref "U14") (pin "P9") (pinfunction "/DQS2_P9") (pintype "passive"))
    )
    (net (code "143") (name "/{slash}SDRDQS3") (class "Default")
      (node (ref "U14") (pin "D9") (pinfunction "/DQS3_D9") (pintype "passive"))
    )
    (net (code "144") (name "/{slash}SDRDQS4") (class "Default")
      (node (ref "U15") (pin "L5") (pinfunction "/DQS0_L5") (pintype "passive"))
    )
    (net (code "145") (name "/{slash}SDRDQS5") (class "Default")
      (node (ref "U15") (pin "G5") (pinfunction "/DQS1_G5") (pintype "passive"))
    )
    (net (code "146") (name "/{slash}SDRDQS6") (class "Default")
      (node (ref "U15") (pin "P9") (pinfunction "/DQS2_P9") (pintype "passive"))
    )
    (net (code "147") (name "/{slash}SDRDQS7") (class "Default")
      (node (ref "U15") (pin "D9") (pinfunction "/DQS3_D9") (pintype "passive"))
    )
    (net (code "149") (name "/{slash}SDRRAS") (class "Default")
      (node (ref "U14") (pin "L2") (pinfunction "/CS1_L2") (pintype "passive"))
    )
    (net (code "150") (name "/{slash}SDRWE") (class "Default")
      (node (ref "R148") (pin "2") (pinfunction "2_2") (pintype "passive"))
      (node (ref "U14") (pin "K1") (pinfunction "CKE0_K1") (pintype "passive"))
    )
    (net (code "151") (name "DRAM_VREF") (class "Default")
      (node (ref "C168") (pin "1") (pinfunction "1_1") (pintype "passive"))
      (node (ref "C169") (pin "1") (pinfunction "1_1") (pintype "passive"))
      (node (ref "C92") (pin "1") (pinfunction "1_1") (pintype "passive"))
      (node (ref "C93") (pin "2") (pinfunction "2_2") (pintype "passive"))
      (node (ref "C94") (pin "1") (pinfunction "1_1") (pintype "passive"))
      (node (ref "C95") (pin "1") (pinfunction "1_1") (pintype "passive"))
      (node (ref "R15") (pin "1") (pinfunction "1_1") (pintype "passive"))
      (node (ref "R9") (pin "2") (pinfunction "2_2") (pintype "passive"))
      (node (ref "U14") (pin "G3") (pinfunction "VREFCA_G3") (pintype "passive"))
      (node (ref "U14") (pin "J9") (pinfunction "VREFDQ_J9") (pintype "passive"))
      (node (ref "U15") (pin "G3") (pinfunction "VREFCA_G3") (pintype "passive"))
      (node (ref "U15") (pin "J9") (pinfunction "VREFDQ_J9") (pintype "passive"))
    )
    (net (code "152") (name "GND") (class "Default")
      (node (ref "C129") (pin "1") (pinfunction "1_1") (pintype "passive"))
      (node (ref "C131") (pin "1") (pinfunction "1_1") (pintype "passive"))
      (node (ref "C132") (pin "2") (pinfunction "2_2") (pintype "passive"))
      (node (ref "C134") (pin "1") (pinfunction "1_1") (pintype "passive"))
      (node (ref "C138") (pin "2") (pinfunction "2_2") (pintype "passive"))
      (node (ref "C141") (pin "2") (pinfunction "2_2") (pintype "passive"))
      (node (ref "C142") (pin "2") (pinfunction "2_2") (pintype "passive"))
      (node (ref "C144") (pin "2") (pinfunction "2_2") (pintype "passive"))
      (node (ref "C146") (pin "2") (pinfunction "2_2") (pintype "passive"))
      (node (ref "C149") (pin "1") (pinfunction "1_1") (pintype "passive"))
      (node (ref "C15") (pin "1") (pinfunction "1_1") (pintype "passive"))
      (node (ref "C151") (pin "1") (pinfunction "1_1") (pintype "passive"))
      (node (ref "C152") (pin "1") (pinfunction "1_1") (pintype "passive"))
      (node (ref "C153") (pin "1") (pinfunction "1_1") (pintype "passive"))
      (node (ref "C154") (pin "1") (pinfunction "1_1") (pintype "passive"))
      (node (ref "C156") (pin "1") (pinfunction "1_1") (pintype "passive"))
      (node (ref "C157") (pin "2") (pinfunction "2_2") (pintype "passive"))
      (node (ref "C158") (pin "2") (pinfunction "2_2") (pintype "passive"))
      (node (ref "C159") (pin "2") (pinfunction "2_2") (pintype "passive"))
      (node (ref "C160") (pin "2") (pinfunction "2_2") (pintype "passive"))
      (node (ref "C161") (pin "2") (pinfunction "2_2") (pintype "passive"))
      (node (ref "C162") (pin "2") (pinfunction "2_2") (pintype "passive"))
      (node (ref "C163") (pin "2") (pinfunction "2_2") (pintype "passive"))
      (node (ref "C164") (pin "1") (pinfunction "1_1") (pintype "passive"))
      (node (ref "C165") (pin "1") (pinfunction "1_1") (pintype "passive"))
      (node (ref "C166") (pin "1") (pinfunction "1_1") (pintype "passive"))
      (node (ref "C167") (pin "1") (pinfunction "1_1") (pintype "passive"))
      (node (ref "C168") (pin "2") (pinfunction "2_2") (pintype "passive"))
      (node (ref "C169") (pin "2") (pinfunction "2_2") (pintype "passive"))
      (node (ref "C170") (pin "2") (pinfunction "2_2") (pintype "passive"))
      (node (ref "C171") (pin "1") (pinfunction "1_1") (pintype "passive"))
      (node (ref "C172") (pin "1") (pinfunction "1_1") (pintype "passive"))
      (node (ref "C173") (pin "1") (pinfunction "1_1") (pintype "passive"))
      (node (ref "C174") (pin "1") (pinfunction "1_1") (pintype "passive"))
      (node (ref "C175") (pin "1") (pinfunction "1_1") (pintype "passive"))
      (node (ref "C21") (pin "1") (pinfunction "1_1") (pintype "passive"))
      (node (ref "C22") (pin "1") (pinfunction "1_1") (pintype "passive"))
      (node (ref "C23") (pin "1") (pinfunction "1_1") (pintype "passive"))
      (node (ref "C24") (pin "1") (pinfunction "1_1") (pintype "passive"))
      (node (ref "C31") (pin "1") (pinfunction "1_1") (pintype "passive"))
      (node (ref "C85") (pin "2") (pinfunction "2_2") (pintype "passive"))
      (node (ref "C93") (pin "1") (pinfunction "1_1") (pintype "passive"))
      (node (ref "C94") (pin "2") (pinfunction "2_2") (pintype "passive"))
      (node (ref "C95") (pin "2") (pinfunction "2_2") (pintype "passive"))
      (node (ref "R148") (pin "1") (pinfunction "1_1") (pintype "passive"))
      (node (ref "R149") (pin "1") (pinfunction "1_1") (pintype "passive"))
      (node (ref "R15") (pin "2") (pinfunction "2_2") (pintype "passive"))
      (node (ref "R162") (pin "2") (pinfunction "2_2") (pintype "passive"))
      (node (ref "R165") (pin "2") (pinfunction "2_2") (pintype "passive"))
      (node (ref "R166") (pin "2") (pinfunction "2_2") (pintype "passive"))
      (node (ref "R167") (pin "2") (pinfunction "2_2") (pintype "passive"))
      (node (ref "R589") (pin "1") (pinfunction "1_1") (pintype "passive"))
      (node (ref "R590") (pin "1") (pinfunction "1_1") (pintype "passive"))
      (node (ref "U10") (pin "4") (pinfunction "VSS_4") (pintype "power_in"))
      (node (ref "U14") (pin "C2") (pinfunction "VSS_C2") (pintype "passive"))
      (node (ref "U14") (pin "C5") (pinfunction "VSS_C5") (pintype "passive"))
      (node (ref "U14") (pin "C6") (pinfunction "VSS_C6") (pintype "passive"))
      (node (ref "U14") (pin "C9") (pinfunction "VSS_C9") (pintype "passive"))
      (node (ref "U14") (pin "D1") (pinfunction "VSS_D1") (pintype "passive"))
      (node (ref "U14") (pin "D10") (pinfunction "VSS_D10") (pintype "passive"))
      (node (ref "U14") (pin "E1") (pinfunction "VSS_E1") (pintype "passive"))
      (node (ref "U14") (pin "E10") (pinfunction "VSS_E10") (pintype "passive"))
      (node (ref "U14") (pin "F5") (pinfunction "VSS_F5") (pintype "passive"))
      (node (ref "U14") (pin "G10") (pinfunction "VSS_G10") (pintype "passive"))
      (node (ref "U14") (pin "H2") (pinfunction "VSS_H2") (pintype "passive"))
      (node (ref "U14") (pin "J1") (pinfunction "VSS_J1") (pintype "passive"))
      (node (ref "U14") (pin "J5") (pinfunction "VSS_J5") (pintype "passive"))
      (node (ref "U14") (pin "J8") (pinfunction "VSS_J8") (pintype "passive"))
      (node (ref "U14") (pin "L10") (pinfunction "VSS_L10") (pintype "passive"))
      (node (ref "U14") (pin "M5") (pinfunction "VSS_M5") (pintype "passive"))
      (node (ref "U14") (pin "N1") (pinfunction "VSS_N1") (pintype "passive"))
      (node (ref "U14") (pin "N10") (pinfunction "VSS_N10") (pintype "passive"))
      (node (ref "U14") (pin "P1") (pinfunction "VSS_P1") (pintype "passive"))
      (node (ref "U14") (pin "P10") (pinfunction "VSS_P10") (pintype "passive"))
      (node (ref "U14") (pin "R2") (pinfunction "VSS_R2") (pintype "passive"))
      (node (ref "U14") (pin "R5") (pinfunction "VSS_R5") (pintype "passive"))
      (node (ref "U14") (pin "R6") (pinfunction "VSS_R6") (pintype "passive"))
      (node (ref "U14") (pin "R9") (pinfunction "VSS_R9") (pintype "passive"))
      (node (ref "U15") (pin "C2") (pinfunction "VSS_C2") (pintype "passive"))
      (node (ref "U15") (pin "C5") (pinfunction "VSS_C5") (pintype "passive"))
      (node (ref "U15") (pin "C6") (pinfunction "VSS_C6") (pintype "passive"))
      (node (ref "U15") (pin "C9") (pinfunction "VSS_C9") (pintype "passive"))
      (node (ref "U15") (pin "D1") (pinfunction "VSS_D1") (pintype "passive"))
      (node (ref "U15") (pin "D10") (pinfunction "VSS_D10") (pintype "passive"))
      (node (ref "U15") (pin "E1") (pinfunction "VSS_E1") (pintype "passive"))
      (node (ref "U15") (pin "E10") (pinfunction "VSS_E10") (pintype "passive"))
      (node (ref "U15") (pin "F5") (pinfunction "VSS_F5") (pintype "passive"))
      (node (ref "U15") (pin "G10") (pinfunction "VSS_G10") (pintype "passive"))
      (node (ref "U15") (pin "H2") (pinfunction "VSS_H2") (pintype "passive"))
      (node (ref "U15") (pin "J1") (pinfunction "VSS_J1") (pintype "passive"))
      (node (ref "U15") (pin "J5") (pinfunction "VSS_J5") (pintype "passive"))
      (node (ref "U15") (pin "J8") (pinfunction "VSS_J8") (pintype "passive"))
      (node (ref "U15") (pin "L10") (pinfunction "VSS_L10") (pintype "passive"))
      (node (ref "U15") (pin "M5") (pinfunction "VSS_M5") (pintype "passive"))
      (node (ref "U15") (pin "N1") (pinfunction "VSS_N1") (pintype "passive"))
      (node (ref "U15") (pin "N10") (pinfunction "VSS_N10") (pintype "passive"))
      (node (ref "U15") (pin "P1") (pinfunction "VSS_P1") (pintype "passive"))
      (node (ref "U15") (pin "P10") (pinfunction "VSS_P10") (pintype "passive"))
      (node (ref "U15") (pin "R2") (pinfunction "VSS_R2") (pintype "passive"))
      (node (ref "U15") (pin "R5") (pinfunction "VSS_R5") (pintype "passive"))
      (node (ref "U15") (pin "R6") (pinfunction "VSS_R6") (pintype "passive"))
      (node (ref "U15") (pin "R9") (pinfunction "VSS_R9") (pintype "passive"))
      (node (ref "U7") (pin "AA4") (pinfunction "VSSQ_AA4") (pintype "passive"))
      (node (ref "U7") (pin "AA6") (pinfunction "VSSQ_AA6") (pintype "passive"))
      (node (ref "U7") (pin "K4") (pinfunction "VSSQ_K4") (pintype "passive"))
      (node (ref "U7") (pin "M7") (pinfunction "VSS_M7") (pintype "passive"))
      (node (ref "U7") (pin "P5") (pinfunction "VSS_P5") (pintype "passive"))
      (node (ref "U7") (pin "R10") (pinfunction "VSS_R10") (pintype "passive"))
      (node (ref "U7") (pin "U8") (pinfunction "VSS_U8") (pintype "passive"))
      (node (ref "U7") (pin "Y2") (pinfunction "VSSQ_Y2") (pintype "passive"))
      (node (ref "U7") (pin "Y5") (pinfunction "VSSQ_Y5") (pintype "passive"))
    )
    (net (code "153") (name "Net-(R117-Pad2)") (class "Default")
      (node (ref "R117") (pin "2") (pinfunction "2_2") (pintype "passive"))
      (node (ref "R52") (pin "1") (pinfunction "1_1") (pintype "passive"))
      (node (ref "U7") (pin "U5") (pinfunction "NC_U5") (pintype "passive"))
    )
    (net (code "154") (name "Net-(U7-CLK)") (class "Default")
      (node (ref "R58") (pin "1") (pinfunction "1_1") (pintype "passive"))
      (node (ref "U7") (pin "W6") (pinfunction "CLK_W6") (pintype "passive"))
    )
    (net (code "155") (name "Net-(U7-VDDi)") (class "Default")
      (node (ref "C22") (pin "2") (pinfunction "2_2") (pintype "passive"))
      (node (ref "U7") (pin "K2") (pinfunction "VDDi_K2") (pintype "passive"))
    )
    (net (code "156") (name "Net-(U10-~{HOLD})") (class "Default")
      (node (ref "R163") (pin "1") (pinfunction "1_1") (pintype "passive"))
      (node (ref "U10") (pin "7") (pinfunction "~{HOLD}_7") (pintype "passive"))
    )
    (net (code "157") (name "Net-(U10-~{W})") (class "Default")
      (node (ref "R254") (pin "2") (pinfunction "2_2") (pintype "passive"))
      (node (ref "R356") (pin "1") (pinfunction "1_1") (pintype "passive"))
      (node (ref "U10") (pin "3") (pinfunction "~{W}_3") (pintype "passive"))
    )
    (net (code "158") (name "Net-(U14-ZQ0)") (class "Default")
      (node (ref "R162") (pin "1") (pinfunction "1_1") (pintype "passive"))
      (node (ref "U14") (pin "D3") (pinfunction "ZQ0_D3") (pintype "passive"))
    )
    (net (code "159") (name "Net-(U14-ZQ1)") (class "Default")
      (node (ref "R166") (pin "1") (pinfunction "1_1") (pintype "passive"))
      (node (ref "U14") (pin "C3") (pinfunction "ZQ1_C3") (pintype "passive"))
    )
    (net (code "160") (name "Net-(U15-ZQ0)") (class "Default")
      (node (ref "R165") (pin "1") (pinfunction "1_1") (pintype "passive"))
      (node (ref "U15") (pin "D3") (pinfunction "ZQ0_D3") (pintype "passive"))
    )
    (net (code "161") (name "Net-(U15-ZQ1)") (class "Default")
      (node (ref "R167") (pin "1") (pinfunction "1_1") (pintype "passive"))
      (node (ref "U15") (pin "C3") (pinfunction "ZQ1_C3") (pintype "passive"))
    )
    (net (code "162") (name "VCC_1V8") (class "Default")
      (node (ref "RL5") (pin "2") (pinfunction "2_2") (pintype "passive"))
    )
    (net (code "163") (name "VCC_3V") (class "Default")
      (node (ref "C15") (pin "2") (pinfunction "2_2") (pintype "passive"))
      (node (ref "C170") (pin "1") (pinfunction "1_1") (pintype "passive"))
      (node (ref "C21") (pin "2") (pinfunction "2_2") (pintype "passive"))
      (node (ref "C23") (pin "2") (pinfunction "2_2") (pintype "passive"))
      (node (ref "C24") (pin "2") (pinfunction "2_2") (pintype "passive"))
      (node (ref "C85") (pin "1") (pinfunction "1_1") (pintype "passive"))
      (node (ref "R131") (pin "1") (pinfunction "1_1") (pintype "passive"))
      (node (ref "R153") (pin "2") (pinfunction "2_2") (pintype "passive"))
      (node (ref "R155") (pin "2") (pinfunction "2_2") (pintype "passive"))
      (node (ref "R158") (pin "2") (pinfunction "2_2") (pintype "passive"))
      (node (ref "R161") (pin "2") (pinfunction "2_2") (pintype "passive"))
      (node (ref "R22") (pin "2") (pinfunction "2_2") (pintype "passive"))
      (node (ref "R23") (pin "2") (pinfunction "2_2") (pintype "passive"))
      (node (ref "R28") (pin "2") (pinfunction "2_2") (pintype "passive"))
      (node (ref "R38") (pin "2") (pinfunction "2_2") (pintype "passive"))
      (node (ref "R52") (pin "2") (pinfunction "2_2") (pintype "passive"))
      (node (ref "R57") (pin "2") (pinfunction "2_2") (pintype "passive"))
      (node (ref "U7") (pin "AA3") (pinfunction "VCCQ_AA3") (pintype "passive"))
      (node (ref "U7") (pin "AA5") (pinfunction "VCCQ_AA5") (pintype "passive"))
      (node (ref "U7") (pin "K6") (pinfunction "VCCQ_K6") (pintype "passive"))
      (node (ref "U7") (pin "M6") (pinfunction "VCC_M6") (pintype "passive"))
      (node (ref "U7") (pin "N5") (pinfunction "VCC_N5") (pintype "passive"))
      (node (ref "U7") (pin "T10") (pinfunction "VCC_T10") (pintype "passive"))
      (node (ref "U7") (pin "U9") (pinfunction "VCC_U9") (pintype "passive"))
      (node (ref "U7") (pin "W4") (pinfunction "VCCQ_W4") (pintype "passive"))
      (node (ref "U7") (pin "Y4") (pinfunction "VCCQ_Y4") (pintype "passive"))
    )
    (net (code "164") (name "VDD_DRAM_1.2V") (class "Default")
      (node (ref "C132") (pin "1") (pinfunction "1_1") (pintype "passive"))
      (node (ref "C138") (pin "1") (pinfunction "1_1") (pintype "passive"))
      (node (ref "C141") (pin "1") (pinfunction "1_1") (pintype "passive"))
      (node (ref "C142") (pin "1") (pinfunction "1_1") (pintype "passive"))
      (node (ref "C144") (pin "1") (pinfunction "1_1") (pintype "passive"))
      (node (ref "C146") (pin "1") (pinfunction "1_1") (pintype "passive"))
      (node (ref "C149") (pin "2") (pinfunction "2_2") (pintype "passive"))
      (node (ref "C151") (pin "2") (pinfunction "2_2") (pintype "passive"))
      (node (ref "C152") (pin "2") (pinfunction "2_2") (pintype "passive"))
      (node (ref "C156") (pin "2") (pinfunction "2_2") (pintype "passive"))
      (node (ref "C157") (pin "1") (pinfunction "1_1") (pintype "passive"))
      (node (ref "C158") (pin "1") (pinfunction "1_1") (pintype "passive"))
      (node (ref "C159") (pin "1") (pinfunction "1_1") (pintype "passive"))
      (node (ref "C161") (pin "1") (pinfunction "1_1") (pintype "passive"))
      (node (ref "C162") (pin "1") (pinfunction "1_1") (pintype "passive"))
      (node (ref "C163") (pin "1") (pinfunction "1_1") (pintype "passive"))
      (node (ref "C164") (pin "2") (pinfunction "2_2") (pintype "passive"))
      (node (ref "C165") (pin "2") (pinfunction "2_2") (pintype "passive"))
      (node (ref "C166") (pin "2") (pinfunction "2_2") (pintype "passive"))
      (node (ref "C167") (pin "2") (pinfunction "2_2") (pintype "passive"))
      (node (ref "C172") (pin "2") (pinfunction "2_2") (pintype "passive"))
      (node (ref "C173") (pin "2") (pinfunction "2_2") (pintype "passive"))
      (node (ref "C174") (pin "2") (pinfunction "2_2") (pintype "passive"))
      (node (ref "C175") (pin "2") (pinfunction "2_2") (pintype "passive"))
      (node (ref "C92") (pin "2") (pinfunction "2_2") (pintype "passive"))
      (node (ref "R9") (pin "1") (pinfunction "1_1") (pintype "passive"))
      (node (ref "RL10") (pin "1") (pinfunction "1_1") (pintype "passive"))
      (node (ref "U14") (pin "B5") (pinfunction "VDD2_B5") (pintype "passive"))
      (node (ref "U14") (pin "C10") (pinfunction "VDDQ_C10") (pintype "passive"))
      (node (ref "U14") (pin "C7") (pinfunction "VDDQ_C7") (pintype "passive"))
      (node (ref "U14") (pin "D2") (pinfunction "VDD2_D2") (pintype "passive"))
      (node (ref "U14") (pin "D5") (pinfunction "VDDQ_D5") (pintype "passive"))
      (node (ref "U14") (pin "E9") (pinfunction "VDDQ_E9") (pintype "passive"))
      (node (ref "U14") (pin "F1") (pinfunction "VDDCA_F1") (pintype "passive"))
      (node (ref "U14") (pin "F10") (pinfunction "VDDQ_F10") (pintype "passive"))
      (node (ref "U14") (pin "G1") (pinfunction "VDD2_G1") (pintype "passive"))
      (node (ref "U14") (pin "H1") (pinfunction "VDDCA_H1") (pintype "passive"))
      (node (ref "U14") (pin "H6") (pinfunction "VDDQ_H6") (pintype "passive"))
      (node (ref "U14") (pin "J6") (pinfunction "VDDQ_J6") (pintype "passive"))
      (node (ref "U14") (pin "J7") (pinfunction "VDD2_J7") (pintype "passive"))
      (node (ref "U14") (pin "K6") (pinfunction "VDDQ_K6") (pintype "passive"))
      (node (ref "U14") (pin "M10") (pinfunction "VDDQ_M10") (pintype "passive"))
      (node (ref "U14") (pin "N2") (pinfunction "VDDCA_N2") (pintype "passive"))
      (node (ref "U14") (pin "N9") (pinfunction "VDDQ_N9") (pintype "passive"))
      (node (ref "U14") (pin "P2") (pinfunction "VDD2_P2") (pintype "passive"))
      (node (ref "U14") (pin "P5") (pinfunction "VDDQ_P5") (pintype "passive"))
      (node (ref "U14") (pin "R10") (pinfunction "VDDQ_R10") (pintype "passive"))
      (node (ref "U14") (pin "R7") (pinfunction "VDDQ_R7") (pintype "passive"))
      (node (ref "U14") (pin "T5") (pinfunction "VDD2_T5") (pintype "passive"))
      (node (ref "U15") (pin "B5") (pinfunction "VDD2_B5") (pintype "passive"))
      (node (ref "U15") (pin "C10") (pinfunction "VDDQ_C10") (pintype "passive"))
      (node (ref "U15") (pin "C7") (pinfunction "VDDQ_C7") (pintype "passive"))
      (node (ref "U15") (pin "D2") (pinfunction "VDD2_D2") (pintype "passive"))
      (node (ref "U15") (pin "D5") (pinfunction "VDDQ_D5") (pintype "passive"))
      (node (ref "U15") (pin "E9") (pinfunction "VDDQ_E9") (pintype "passive"))
      (node (ref "U15") (pin "F1") (pinfunction "VDDCA_F1") (pintype "passive"))
      (node (ref "U15") (pin "F10") (pinfunction "VDDQ_F10") (pintype "passive"))
      (node (ref "U15") (pin "G1") (pinfunction "VDD2_G1") (pintype "passive"))
      (node (ref "U15") (pin "H1") (pinfunction "VDDCA_H1") (pintype "passive"))
      (node (ref "U15") (pin "H6") (pinfunction "VDDQ_H6") (pintype "passive"))
      (node (ref "U15") (pin "J6") (pinfunction "VDDQ_J6") (pintype "passive"))
      (node (ref "U15") (pin "J7") (pinfunction "VDD2_J7") (pintype "passive"))
      (node (ref "U15") (pin "K6") (pinfunction "VDDQ_K6") (pintype "passive"))
      (node (ref "U15") (pin "M10") (pinfunction "VDDQ_M10") (pintype "passive"))
      (node (ref "U15") (pin "N2") (pinfunction "VDDCA_N2") (pintype "passive"))
      (node (ref "U15") (pin "N9") (pinfunction "VDDQ_N9") (pintype "passive"))
      (node (ref "U15") (pin "P2") (pinfunction "VDD2_P2") (pintype "passive"))
      (node (ref "U15") (pin "P5") (pinfunction "VDDQ_P5") (pintype "passive"))
      (node (ref "U15") (pin "R10") (pinfunction "VDDQ_R10") (pintype "passive"))
      (node (ref "U15") (pin "R7") (pinfunction "VDDQ_R7") (pintype "passive"))
      (node (ref "U15") (pin "T5") (pinfunction "VDD2_T5") (pintype "passive"))
    )
    (net (code "165") (name "VDD_DRAM_1.8V") (class "Default")
      (node (ref "C129") (pin "2") (pinfunction "2_2") (pintype "passive"))
      (node (ref "C131") (pin "2") (pinfunction "2_2") (pintype "passive"))
      (node (ref "C134") (pin "2") (pinfunction "2_2") (pintype "passive"))
      (node (ref "C153") (pin "2") (pinfunction "2_2") (pintype "passive"))
      (node (ref "C154") (pin "2") (pinfunction "2_2") (pintype "passive"))
      (node (ref "C171") (pin "2") (pinfunction "2_2") (pintype "passive"))
      (node (ref "RL5") (pin "1") (pinfunction "1_1") (pintype "passive"))
      (node (ref "U14") (pin "B6") (pinfunction "VDD1_B6") (pintype "passive"))
      (node (ref "U14") (pin "C1") (pinfunction "VDD1_C1") (pintype "passive"))
      (node (ref "U14") (pin "R1") (pinfunction "VDD1_R1") (pintype "passive"))
      (node (ref "U14") (pin "T6") (pinfunction "VDD1_T6") (pintype "passive"))
      (node (ref "U15") (pin "B6") (pinfunction "VDD1_B6") (pintype "passive"))
      (node (ref "U15") (pin "C1") (pinfunction "VDD1_C1") (pintype "passive"))
      (node (ref "U15") (pin "R1") (pinfunction "VDD1_R1") (pintype "passive"))
      (node (ref "U15") (pin "T6") (pinfunction "VDD1_T6") (pintype "passive"))
    )
    (net (code "166") (name "VDD_SDR_1.2V") (class "Default")
      (node (ref "RL10") (pin "2") (pinfunction "2_2") (pintype "passive"))
    )
    (net (code "167") (name "VDD_UBSPI") (class "Default")
      (node (ref "C160") (pin "1") (pinfunction "1_1") (pintype "passive"))
      (node (ref "C31") (pin "2") (pinfunction "2_2") (pintype "passive"))
      (node (ref "R131") (pin "2") (pinfunction "2_2") (pintype "passive"))
      (node (ref "R163") (pin "2") (pinfunction "2_2") (pintype "passive"))
      (node (ref "R356") (pin "2") (pinfunction "2_2") (pintype "passive"))
      (node (ref "U10") (pin "8") (pinfunction "VCC_8") (pintype "power_in"))
    )
    (net (code "168") (name "unconnected-(U7-A1-PadL4)") (class "Default")
      (node (ref "U7") (pin "L4") (pinfunction "A1_L4") (pintype "passive"))
    )
    (net (code "169") (name "unconnected-(U7-NC-PadA4)") (class "Default")
      (node (ref "U7") (pin "A4") (pinfunction "NC_A4") (pintype "passive+no_connect"))
    )
    (net (code "170") (name "unconnected-(U7-NC-PadA6)") (class "Default")
      (node (ref "U7") (pin "A6") (pinfunction "NC_A6") (pintype "passive+no_connect"))
    )
    (net (code "171") (name "unconnected-(U7-NC-PadA9)") (class "Default")
      (node (ref "U7") (pin "A9") (pinfunction "NC_A9") (pintype "passive+no_connect"))
    )
    (net (code "172") (name "unconnected-(U7-NC-PadA11)") (class "Default")
      (node (ref "U7") (pin "A11") (pinfunction "NC_A11") (pintype "passive+no_connect"))
    )
    (net (code "173") (name "unconnected-(U7-NC-PadAA1)") (class "Default")
      (node (ref "U7") (pin "AA1") (pinfunction "NC_AA1") (pintype "passive+no_connect"))
    )
    (net (code "174") (name "unconnected-(U7-NC-PadAA2)") (class "Default")
      (node (ref "U7") (pin "AA2") (pinfunction "NC_AA2") (pintype "passive+no_connect"))
    )
    (net (code "175") (name "unconnected-(U7-NC-PadAA7)") (class "Default")
      (node (ref "U7") (pin "AA7") (pinfunction "NC_AA7") (pintype "passive+no_connect"))
    )
    (net (code "176") (name "unconnected-(U7-NC-PadAA8)") (class "Default")
      (node (ref "U7") (pin "AA8") (pinfunction "NC_AA8") (pintype "passive+no_connect"))
    )
    (net (code "177") (name "unconnected-(U7-NC-PadAA9)") (class "Default")
      (node (ref "U7") (pin "AA9") (pinfunction "NC_AA9") (pintype "passive+no_connect"))
    )
    (net (code "178") (name "unconnected-(U7-NC-PadAA10)") (class "Default")
      (node (ref "U7") (pin "AA10") (pinfunction "NC_AA10") (pintype "passive+no_connect"))
    )
    (net (code "179") (name "unconnected-(U7-NC-PadAA11)") (class "Default")
      (node (ref "U7") (pin "AA11") (pinfunction "NC_AA11") (pintype "passive+no_connect"))
    )
    (net (code "180") (name "unconnected-(U7-NC-PadAA12)") (class "Default")
      (node (ref "U7") (pin "AA12") (pinfunction "NC_AA12") (pintype "passive+no_connect"))
    )
    (net (code "181") (name "unconnected-(U7-NC-PadAA13)") (class "Default")
      (node (ref "U7") (pin "AA13") (pinfunction "NC_AA13") (pintype "passive+no_connect"))
    )
    (net (code "182") (name "unconnected-(U7-NC-PadAA14)") (class "Default")
      (node (ref "U7") (pin "AA14") (pinfunction "NC_AA14") (pintype "passive+no_connect"))
    )
    (net (code "183") (name "unconnected-(U7-NC-PadAE1)") (class "Default")
      (node (ref "U7") (pin "AE1") (pinfunction "NC_AE1") (pintype "passive+no_connect"))
    )
    (net (code "184") (name "unconnected-(U7-NC-PadAE14)") (class "Default")
      (node (ref "U7") (pin "AE14") (pinfunction "NC_AE14") (pintype "passive+no_connect"))
    )
    (net (code "185") (name "unconnected-(U7-NC-PadAG2)") (class "Default")
      (node (ref "U7") (pin "AG2") (pinfunction "NC_AG2") (pintype "passive+no_connect"))
    )
    (net (code "186") (name "unconnected-(U7-NC-PadAG13)") (class "Default")
      (node (ref "U7") (pin "AG13") (pinfunction "NC_AG13") (pintype "passive+no_connect"))
    )
    (net (code "187") (name "unconnected-(U7-NC-PadAH4)") (class "Default")
      (node (ref "U7") (pin "AH4") (pinfunction "NC_AH4") (pintype "passive+no_connect"))
    )
    (net (code "188") (name "unconnected-(U7-NC-PadAH6)") (class "Default")
      (node (ref "U7") (pin "AH6") (pinfunction "NC_AH6") (pintype "passive+no_connect"))
    )
    (net (code "189") (name "unconnected-(U7-NC-PadAH9)") (class "Default")
      (node (ref "U7") (pin "AH9") (pinfunction "NC_AH9") (pintype "passive+no_connect"))
    )
    (net (code "190") (name "unconnected-(U7-NC-PadAH11)") (class "Default")
      (node (ref "U7") (pin "AH11") (pinfunction "NC_AH11") (pintype "passive+no_connect"))
    )
    (net (code "191") (name "unconnected-(U7-NC-PadB2)") (class "Default")
      (node (ref "U7") (pin "B2") (pinfunction "NC_B2") (pintype "passive+no_connect"))
    )
    (net (code "192") (name "unconnected-(U7-NC-PadB13)") (class "Default")
      (node (ref "U7") (pin "B13") (pinfunction "NC_B13") (pintype "passive+no_connect"))
    )
    (net (code "193") (name "unconnected-(U7-NC-PadD1)") (class "Default")
      (node (ref "U7") (pin "D1") (pinfunction "NC_D1") (pintype "passive+no_connect"))
    )
    (net (code "194") (name "unconnected-(U7-NC-PadD14)") (class "Default")
      (node (ref "U7") (pin "D14") (pinfunction "NC_D14") (pintype "passive+no_connect"))
    )
    (net (code "195") (name "unconnected-(U7-NC-PadH1)") (class "Default")
      (node (ref "U7") (pin "H1") (pinfunction "NC_H1") (pintype "passive+no_connect"))
    )
    (net (code "196") (name "unconnected-(U7-NC-PadH2)") (class "Default")
      (node (ref "U7") (pin "H2") (pinfunction "NC_H2") (pintype "passive+no_connect"))
    )
    (net (code "197") (name "unconnected-(U7-NC-PadH6)") (class "Default")
      (node (ref "U7") (pin "H6") (pinfunction "NC_H6") (pintype "passive+no_connect"))
    )
    (net (code "198") (name "unconnected-(U7-NC-PadH7)") (class "Default")
      (node (ref "U7") (pin "H7") (pinfunction "NC_H7") (pintype "passive+no_connect"))
    )
    (net (code "199") (name "unconnected-(U7-NC-PadH8)") (class "Default")
      (node (ref "U7") (pin "H8") (pinfunction "NC_H8") (pintype "passive+no_connect"))
    )
    (net (code "200") (name "unconnected-(U7-NC-PadH9)") (class "Default")
      (node (ref "U7") (pin "H9") (pinfunction "NC_H9") (pintype "passive+no_connect"))
    )
    (net (code "201") (name "unconnected-(U7-NC-PadH10)") (class "Default")
      (node (ref "U7") (pin "H10") (pinfunction "NC_H10") (pintype "passive+no_connect"))
    )
    (net (code "202") (name "unconnected-(U7-NC-PadH11)") (class "Default")
      (node (ref "U7") (pin "H11") (pinfunction "NC_H11") (pintype "passive+no_connect"))
    )
    (net (code "203") (name "unconnected-(U7-NC-PadH12)") (class "Default")
      (node (ref "U7") (pin "H12") (pinfunction "NC_H12") (pintype "passive+no_connect"))
    )
    (net (code "204") (name "unconnected-(U7-NC-PadH13)") (class "Default")
      (node (ref "U7") (pin "H13") (pinfunction "NC_H13") (pintype "passive+no_connect"))
    )
    (net (code "205") (name "unconnected-(U7-NC-PadH14)") (class "Default")
      (node (ref "U7") (pin "H14") (pinfunction "NC_H14") (pintype "passive+no_connect"))
    )
    (net (code "206") (name "unconnected-(U7-NC-PadJ1)") (class "Default")
      (node (ref "U7") (pin "J1") (pinfunction "NC_J1") (pintype "passive+no_connect"))
    )
    (net (code "207") (name "unconnected-(U7-NC-PadJ7)") (class "Default")
      (node (ref "U7") (pin "J7") (pinfunction "NC_J7") (pintype "passive+no_connect"))
    )
    (net (code "208") (name "unconnected-(U7-NC-PadJ8)") (class "Default")
      (node (ref "U7") (pin "J8") (pinfunction "NC_J8") (pintype "passive+no_connect"))
    )
    (net (code "209") (name "unconnected-(U7-NC-PadJ9)") (class "Default")
      (node (ref "U7") (pin "J9") (pinfunction "NC_J9") (pintype "passive+no_connect"))
    )
    (net (code "210") (name "unconnected-(U7-NC-PadJ10)") (class "Default")
      (node (ref "U7") (pin "J10") (pinfunction "NC_J10") (pintype "passive+no_connect"))
    )
    (net (code "211") (name "unconnected-(U7-NC-PadJ11)") (class "Default")
      (node (ref "U7") (pin "J11") (pinfunction "NC_J11") (pintype "passive+no_connect"))
    )
    (net (code "212") (name "unconnected-(U7-NC-PadJ12)") (class "Default")
      (node (ref "U7") (pin "J12") (pinfunction "NC_J12") (pintype "passive+no_connect"))
    )
    (net (code "213") (name "unconnected-(U7-NC-PadJ13)") (class "Default")
      (node (ref "U7") (pin "J13") (pinfunction "NC_J13") (pintype "passive+no_connect"))
    )
    (net (code "214") (name "unconnected-(U7-NC-PadJ14)") (class "Default")
      (node (ref "U7") (pin "J14") (pinfunction "NC_J14") (pintype "passive+no_connect"))
    )
    (net (code "215") (name "unconnected-(U7-NC-PadK1)") (class "Default")
      (node (ref "U7") (pin "K1") (pinfunction "NC_K1") (pintype "passive+no_connect"))
    )
    (net (code "216") (name "unconnected-(U7-NC-PadK3)") (class "Default")
      (node (ref "U7") (pin "K3") (pinfunction "NC_K3") (pintype "passive+no_connect"))
    )
    (net (code "217") (name "unconnected-(U7-NC-PadK5)") (class "Default")
      (node (ref "U7") (pin "K5") (pinfunction "NC_K5") (pintype "passive+no_connect"))
    )
    (net (code "218") (name "unconnected-(U7-NC-PadK7)") (class "Default")
      (node (ref "U7") (pin "K7") (pinfunction "NC_K7") (pintype "passive+no_connect"))
    )
    (net (code "219") (name "unconnected-(U7-NC-PadK8)") (class "Default")
      (node (ref "U7") (pin "K8") (pinfunction "NC_K8") (pintype "passive+no_connect"))
    )
    (net (code "220") (name "unconnected-(U7-NC-PadK9)") (class "Default")
      (node (ref "U7") (pin "K9") (pinfunction "NC_K9") (pintype "passive+no_connect"))
    )
    (net (code "221") (name "unconnected-(U7-NC-PadK10)") (class "Default")
      (node (ref "U7") (pin "K10") (pinfunction "NC_K10") (pintype "passive+no_connect"))
    )
    (net (code "222") (name "unconnected-(U7-NC-PadK11)") (class "Default")
      (node (ref "U7") (pin "K11") (pinfunction "NC_K11") (pintype "passive+no_connect"))
    )
    (net (code "223") (name "unconnected-(U7-NC-PadK12)") (class "Default")
      (node (ref "U7") (pin "K12") (pinfunction "NC_K12") (pintype "passive+no_connect"))
    )
    (net (code "224") (name "unconnected-(U7-NC-PadK13)") (class "Default")
      (node (ref "U7") (pin "K13") (pinfunction "NC_K13") (pintype "passive+no_connect"))
    )
    (net (code "225") (name "unconnected-(U7-NC-PadK14)") (class "Default")
      (node (ref "U7") (pin "K14") (pinfunction "NC_K14") (pintype "passive+no_connect"))
    )
    (net (code "226") (name "unconnected-(U7-NC-PadL1)") (class "Default")
      (node (ref "U7") (pin "L1") (pinfunction "NC_L1") (pintype "passive+no_connect"))
    )
    (net (code "227") (name "unconnected-(U7-NC-PadL2)") (class "Default")
      (node (ref "U7") (pin "L2") (pinfunction "NC_L2") (pintype "passive+no_connect"))
    )
    (net (code "228") (name "unconnected-(U7-NC-PadL3)") (class "Default")
      (node (ref "U7") (pin "L3") (pinfunction "NC_L3") (pintype "passive+no_connect"))
    )
    (net (code "229") (name "unconnected-(U7-NC-PadL12)") (class "Default")
      (node (ref "U7") (pin "L12") (pinfunction "NC_L12") (pintype "passive+no_connect"))
    )
    (net (code "230") (name "unconnected-(U7-NC-PadL13)") (class "Default")
      (node (ref "U7") (pin "L13") (pinfunction "NC_L13") (pintype "passive+no_connect"))
    )
    (net (code "231") (name "unconnected-(U7-NC-PadL14)") (class "Default")
      (node (ref "U7") (pin "L14") (pinfunction "NC_L14") (pintype "passive+no_connect"))
    )
    (net (code "232") (name "unconnected-(U7-NC-PadM1)") (class "Default")
      (node (ref "U7") (pin "M1") (pinfunction "NC_M1") (pintype "passive+no_connect"))
    )
    (net (code "233") (name "unconnected-(U7-NC-PadM2)") (class "Default")
      (node (ref "U7") (pin "M2") (pinfunction "NC_M2") (pintype "passive+no_connect"))
    )
    (net (code "234") (name "unconnected-(U7-NC-PadM3)") (class "Default")
      (node (ref "U7") (pin "M3") (pinfunction "NC_M3") (pintype "passive+no_connect"))
    )
    (net (code "235") (name "unconnected-(U7-NC-PadM5)") (class "Default")
      (node (ref "U7") (pin "M5") (pinfunction "NC_M5") (pintype "passive+no_connect"))
    )
    (net (code "236") (name "unconnected-(U7-NC-PadM8)") (class "Default")
      (node (ref "U7") (pin "M8") (pinfunction "NC_M8") (pintype "passive+no_connect"))
    )
    (net (code "237") (name "unconnected-(U7-NC-PadM9)") (class "Default")
      (node (ref "U7") (pin "M9") (pinfunction "NC_M9") (pintype "passive+no_connect"))
    )
    (net (code "238") (name "unconnected-(U7-NC-PadM10)") (class "Default")
      (node (ref "U7") (pin "M10") (pinfunction "NC_M10") (pintype "passive+no_connect"))
    )
    (net (code "239") (name "unconnected-(U7-NC-PadM12)") (class "Default")
      (node (ref "U7") (pin "M12") (pinfunction "NC_M12") (pintype "passive+no_connect"))
    )
    (net (code "240") (name "unconnected-(U7-NC-PadM13)") (class "Default")
      (node (ref "U7") (pin "M13") (pinfunction "NC_M13") (pintype "passive+no_connect"))
    )
    (net (code "241") (name "unconnected-(U7-NC-PadM14)") (class "Default")
      (node (ref "U7") (pin "M14") (pinfunction "NC_M14") (pintype "passive+no_connect"))
    )
    (net (code "242") (name "unconnected-(U7-NC-PadN1)") (class "Default")
      (node (ref "U7") (pin "N1") (pinfunction "NC_N1") (pintype "passive+no_connect"))
    )
    (net (code "243") (name "unconnected-(U7-NC-PadN2)") (class "Default")
      (node (ref "U7") (pin "N2") (pinfunction "NC_N2") (pintype "passive+no_connect"))
    )
    (net (code "244") (name "unconnected-(U7-NC-PadN3)") (class "Default")
      (node (ref "U7") (pin "N3") (pinfunction "NC_N3") (pintype "passive+no_connect"))
    )
    (net (code "245") (name "unconnected-(U7-NC-PadN10)") (class "Default")
      (node (ref "U7") (pin "N10") (pinfunction "NC_N10") (pintype "passive+no_connect"))
    )
    (net (code "246") (name "unconnected-(U7-NC-PadN12)") (class "Default")
      (node (ref "U7") (pin "N12") (pinfunction "NC_N12") (pintype "passive+no_connect"))
    )
    (net (code "247") (name "unconnected-(U7-NC-PadN13)") (class "Default")
      (node (ref "U7") (pin "N13") (pinfunction "NC_N13") (pintype "passive+no_connect"))
    )
    (net (code "248") (name "unconnected-(U7-NC-PadN14)") (class "Default")
      (node (ref "U7") (pin "N14") (pinfunction "NC_N14") (pintype "passive+no_connect"))
    )
    (net (code "249") (name "unconnected-(U7-NC-PadP1)") (class "Default")
      (node (ref "U7") (pin "P1") (pinfunction "NC_P1") (pintype "passive+no_connect"))
    )
    (net (code "250") (name "unconnected-(U7-NC-PadP2)") (class "Default")
      (node (ref "U7") (pin "P2") (pinfunction "NC_P2") (pintype "passive+no_connect"))
    )
    (net (code "251") (name "unconnected-(U7-NC-PadP3)") (class "Default")
      (node (ref "U7") (pin "P3") (pinfunction "NC_P3") (pintype "passive+no_connect"))
    )
    (net (code "252") (name "unconnected-(U7-NC-PadP10)") (class "Default")
      (node (ref "U7") (pin "P10") (pinfunction "NC_P10") (pintype "passive+no_connect"))
    )
    (net (code "253") (name "unconnected-(U7-NC-PadP12)") (class "Default")
      (node (ref "U7") (pin "P12") (pinfunction "NC_P12") (pintype "passive+no_connect"))
    )
    (net (code "254") (name "unconnected-(U7-NC-PadP13)") (class "Default")
      (node (ref "U7") (pin "P13") (pinfunction "NC_P13") (pintype "passive+no_connect"))
    )
    (net (code "255") (name "unconnected-(U7-NC-PadP14)") (class "Default")
      (node (ref "U7") (pin "P14") (pinfunction "NC_P14") (pintype "passive+no_connect"))
    )
    (net (code "256") (name "unconnected-(U7-NC-PadR1)") (class "Default")
      (node (ref "U7") (pin "R1") (pinfunction "NC_R1") (pintype "passive+no_connect"))
    )
    (net (code "257") (name "unconnected-(U7-NC-PadR2)") (class "Default")
      (node (ref "U7") (pin "R2") (pinfunction "NC_R2") (pintype "passive+no_connect"))
    )
    (net (code "258") (name "unconnected-(U7-NC-PadR3)") (class "Default")
      (node (ref "U7") (pin "R3") (pinfunction "NC_R3") (pintype "passive+no_connect"))
    )
    (net (code "259") (name "unconnected-(U7-NC-PadR5)") (class "Default")
      (node (ref "U7") (pin "R5") (pinfunction "NC_R5") (pintype "passive+no_connect"))
    )
    (net (code "260") (name "unconnected-(U7-NC-PadR12)") (class "Default")
      (node (ref "U7") (pin "R12") (pinfunction "NC_R12") (pintype "passive+no_connect"))
    )
    (net (code "261") (name "unconnected-(U7-NC-PadR13)") (class "Default")
      (node (ref "U7") (pin "R13") (pinfunction "NC_R13") (pintype "passive+no_connect"))
    )
    (net (code "262") (name "unconnected-(U7-NC-PadR14)") (class "Default")
      (node (ref "U7") (pin "R14") (pinfunction "NC_R14") (pintype "passive+no_connect"))
    )
    (net (code "263") (name "unconnected-(U7-NC-PadT1)") (class "Default")
      (node (ref "U7") (pin "T1") (pinfunction "NC_T1") (pintype "passive+no_connect"))
    )
    (net (code "264") (name "unconnected-(U7-NC-PadT2)") (class "Default")
      (node (ref "U7") (pin "T2") (pinfunction "NC_T2") (pintype "passive+no_connect"))
    )
    (net (code "265") (name "unconnected-(U7-NC-PadT3)") (class "Default")
      (node (ref "U7") (pin "T3") (pinfunction "NC_T3") (pintype "passive+no_connect"))
    )
    (net (code "266") (name "unconnected-(U7-NC-PadT5)") (class "Default")
      (node (ref "U7") (pin "T5") (pinfunction "NC_T5") (pintype "passive+no_connect"))
    )
    (net (code "267") (name "unconnected-(U7-NC-PadT12)") (class "Default")
      (node (ref "U7") (pin "T12") (pinfunction "NC_T12") (pintype "passive+no_connect"))
    )
    (net (code "268") (name "unconnected-(U7-NC-PadT13)") (class "Default")
      (node (ref "U7") (pin "T13") (pinfunction "NC_T13") (pintype "passive+no_connect"))
    )
    (net (code "269") (name "unconnected-(U7-NC-PadT14)") (class "Default")
      (node (ref "U7") (pin "T14") (pinfunction "NC_T14") (pintype "passive+no_connect"))
    )
    (net (code "270") (name "unconnected-(U7-NC-PadU1)") (class "Default")
      (node (ref "U7") (pin "U1") (pinfunction "NC_U1") (pintype "passive+no_connect"))
    )
    (net (code "271") (name "unconnected-(U7-NC-PadU2)") (class "Default")
      (node (ref "U7") (pin "U2") (pinfunction "NC_U2") (pintype "passive+no_connect"))
    )
    (net (code "272") (name "unconnected-(U7-NC-PadU3)") (class "Default")
      (node (ref "U7") (pin "U3") (pinfunction "NC_U3") (pintype "passive+no_connect"))
    )
    (net (code "273") (name "unconnected-(U7-NC-PadU6)") (class "Default")
      (node (ref "U7") (pin "U6") (pinfunction "NC_U6") (pintype "passive+no_connect"))
    )
    (net (code "274") (name "unconnected-(U7-NC-PadU7)") (class "Default")
      (node (ref "U7") (pin "U7") (pinfunction "NC_U7") (pintype "passive+no_connect"))
    )
    (net (code "275") (name "unconnected-(U7-NC-PadU10)") (class "Default")
      (node (ref "U7") (pin "U10") (pinfunction "NC_U10") (pintype "passive+no_connect"))
    )
    (net (code "276") (name "unconnected-(U7-NC-PadU12)") (class "Default")
      (node (ref "U7") (pin "U12") (pinfunction "NC_U12") (pintype "passive+no_connect"))
    )
    (net (code "277") (name "unconnected-(U7-NC-PadU13)") (class "Default")
      (node (ref "U7") (pin "U13") (pinfunction "NC_U13") (pintype "passive+no_connect"))
    )
    (net (code "278") (name "unconnected-(U7-NC-PadU14)") (class "Default")
      (node (ref "U7") (pin "U14") (pinfunction "NC_U14") (pintype "passive+no_connect"))
    )
    (net (code "279") (name "unconnected-(U7-NC-PadV1)") (class "Default")
      (node (ref "U7") (pin "V1") (pinfunction "NC_V1") (pintype "passive+no_connect"))
    )
    (net (code "280") (name "unconnected-(U7-NC-PadV2)") (class "Default")
      (node (ref "U7") (pin "V2") (pinfunction "NC_V2") (pintype "passive+no_connect"))
    )
    (net (code "281") (name "unconnected-(U7-NC-PadV3)") (class "Default")
      (node (ref "U7") (pin "V3") (pinfunction "NC_V3") (pintype "passive+no_connect"))
    )
    (net (code "282") (name "unconnected-(U7-NC-PadV12)") (class "Default")
      (node (ref "U7") (pin "V12") (pinfunction "NC_V12") (pintype "passive+no_connect"))
    )
    (net (code "283") (name "unconnected-(U7-NC-PadV13)") (class "Default")
      (node (ref "U7") (pin "V13") (pinfunction "NC_V13") (pintype "passive+no_connect"))
    )
    (net (code "284") (name "unconnected-(U7-NC-PadV14)") (class "Default")
      (node (ref "U7") (pin "V14") (pinfunction "NC_V14") (pintype "passive+no_connect"))
    )
    (net (code "285") (name "unconnected-(U7-NC-PadW1)") (class "Default")
      (node (ref "U7") (pin "W1") (pinfunction "NC_W1") (pintype "passive+no_connect"))
    )
    (net (code "286") (name "unconnected-(U7-NC-PadW2)") (class "Default")
      (node (ref "U7") (pin "W2") (pinfunction "NC_W2") (pintype "passive+no_connect"))
    )
    (net (code "287") (name "unconnected-(U7-NC-PadW3)") (class "Default")
      (node (ref "U7") (pin "W3") (pinfunction "NC_W3") (pintype "passive+no_connect"))
    )
    (net (code "288") (name "unconnected-(U7-NC-PadW7)") (class "Default")
      (node (ref "U7") (pin "W7") (pinfunction "NC_W7") (pintype "passive+no_connect"))
    )
    (net (code "289") (name "unconnected-(U7-NC-PadW8)") (class "Default")
      (node (ref "U7") (pin "W8") (pinfunction "NC_W8") (pintype "passive+no_connect"))
    )
    (net (code "290") (name "unconnected-(U7-NC-PadW9)") (class "Default")
      (node (ref "U7") (pin "W9") (pinfunction "NC_W9") (pintype "passive+no_connect"))
    )
    (net (code "291") (name "unconnected-(U7-NC-PadW10)") (class "Default")
      (node (ref "U7") (pin "W10") (pinfunction "NC_W10") (pintype "passive+no_connect"))
    )
    (net (code "292") (name "unconnected-(U7-NC-PadW11)") (class "Default")
      (node (ref "U7") (pin "W11") (pinfunction "NC_W11") (pintype "passive+no_connect"))
    )
    (net (code "293") (name "unconnected-(U7-NC-PadW12)") (class "Default")
      (node (ref "U7") (pin "W12") (pinfunction "NC_W12") (pintype "passive+no_connect"))
    )
    (net (code "294") (name "unconnected-(U7-NC-PadW13)") (class "Default")
      (node (ref "U7") (pin "W13") (pinfunction "NC_W13") (pintype "passive+no_connect"))
    )
    (net (code "295") (name "unconnected-(U7-NC-PadW14)") (class "Default")
      (node (ref "U7") (pin "W14") (pinfunction "NC_W14") (pintype "passive+no_connect"))
    )
    (net (code "296") (name "unconnected-(U7-NC-PadY1)") (class "Default")
      (node (ref "U7") (pin "Y1") (pinfunction "NC_Y1") (pintype "passive+no_connect"))
    )
    (net (code "297") (name "unconnected-(U7-NC-PadY3)") (class "Default")
      (node (ref "U7") (pin "Y3") (pinfunction "NC_Y3") (pintype "passive+no_connect"))
    )
    (net (code "298") (name "unconnected-(U7-NC-PadY6)") (class "Default")
      (node (ref "U7") (pin "Y6") (pinfunction "NC_Y6") (pintype "passive+no_connect"))
    )
    (net (code "299") (name "unconnected-(U7-NC-PadY7)") (class "Default")
      (node (ref "U7") (pin "Y7") (pinfunction "NC_Y7") (pintype "passive+no_connect"))
    )
    (net (code "300") (name "unconnected-(U7-NC-PadY8)") (class "Default")
      (node (ref "U7") (pin "Y8") (pinfunction "NC_Y8") (pintype "passive+no_connect"))
    )
    (net (code "301") (name "unconnected-(U7-NC-PadY9)") (class "Default")
      (node (ref "U7") (pin "Y9") (pinfunction "NC_Y9") (pintype "passive+no_connect"))
    )
    (net (code "302") (name "unconnected-(U7-NC-PadY10)") (class "Default")
      (node (ref "U7") (pin "Y10") (pinfunction "NC_Y10") (pintype "passive+no_connect"))
    )
    (net (code "303") (name "unconnected-(U7-NC-PadY11)") (class "Default")
      (node (ref "U7") (pin "Y11") (pinfunction "NC_Y11") (pintype "passive+no_connect"))
    )
    (net (code "304") (name "unconnected-(U7-NC-PadY12)") (class "Default")
      (node (ref "U7") (pin "Y12") (pinfunction "NC_Y12") (pintype "passive+no_connect"))
    )
    (net (code "305") (name "unconnected-(U7-NC-PadY13)") (class "Default")
      (node (ref "U7") (pin "Y13") (pinfunction "NC_Y13") (pintype "passive+no_connect"))
    )
    (net (code "306") (name "unconnected-(U7-NC-PadY14)") (class "Default")
      (node (ref "U7") (pin "Y14") (pinfunction "NC_Y14") (pintype "passive+no_connect"))
    )
    (net (code "307") (name "unconnected-(U14-NC-PadB2)") (class "Default")
      (node (ref "U14") (pin "B2") (pinfunction "NC_B2") (pintype "passive"))
    )
    (net (code "308") (name "unconnected-(U14-NC-PadB3)") (class "Default")
      (node (ref "U14") (pin "B3") (pinfunction "NC_B3") (pintype "passive"))
    )
    (net (code "309") (name "unconnected-(U14-NC-PadJ2)") (class "Default")
      (node (ref "U14") (pin "J2") (pinfunction "NC_J2") (pintype "passive"))
    )
    (net (code "310") (name "unconnected-(U14-NC-PadK3)") (class "Default")
      (node (ref "U14") (pin "K3") (pinfunction "NC_K3") (pintype "passive"))
    )
    (net (code "311") (name "unconnected-(U14-NC-PadL3)") (class "Default")
      (node (ref "U14") (pin "L3") (pinfunction "NC_L3") (pintype "passive"))
    )
    (net (code "312") (name "unconnected-(U14-NC-PadR3)") (class "Default")
      (node (ref "U14") (pin "R3") (pinfunction "NC_R3") (pintype "passive"))
    )
    (net (code "313") (name "unconnected-(U14-NC-PadT2)") (class "Default")
      (node (ref "U14") (pin "T2") (pinfunction "NC_T2") (pintype "passive"))
    )
    (net (code "314") (name "unconnected-(U14-NC-PadT3)") (class "Default")
      (node (ref "U14") (pin "T3") (pinfunction "NC_T3") (pintype "passive"))
    )
    (net (code "315") (name "unconnected-(U14-NU-PadA1)") (class "Default")
      (node (ref "U14") (pin "A1") (pinfunction "NU_A1") (pintype "passive"))
    )
    (net (code "316") (name "unconnected-(U14-NU-PadA2)") (class "Default")
      (node (ref "U14") (pin "A2") (pinfunction "NU_A2") (pintype "passive"))
    )
    (net (code "317") (name "unconnected-(U14-NU-PadA9)") (class "Default")
      (node (ref "U14") (pin "A9") (pinfunction "NU_A9") (pintype "passive"))
    )
    (net (code "318") (name "unconnected-(U14-NU-PadA10)") (class "Default")
      (node (ref "U14") (pin "A10") (pinfunction "NU_A10") (pintype "passive"))
    )
    (net (code "319") (name "unconnected-(U14-NU-PadB1)") (class "Default")
      (node (ref "U14") (pin "B1") (pinfunction "NU_B1") (pintype "passive"))
    )
    (net (code "320") (name "unconnected-(U14-NU-PadB10)") (class "Default")
      (node (ref "U14") (pin "B10") (pinfunction "NU_B10") (pintype "passive"))
    )
    (net (code "321") (name "unconnected-(U14-NU-PadT1)") (class "Default")
      (node (ref "U14") (pin "T1") (pinfunction "NU_T1") (pintype "passive"))
    )
    (net (code "322") (name "unconnected-(U14-NU-PadT10)") (class "Default")
      (node (ref "U14") (pin "T10") (pinfunction "NU_T10") (pintype "passive"))
    )
    (net (code "323") (name "unconnected-(U14-NU-PadU1)") (class "Default")
      (node (ref "U14") (pin "U1") (pinfunction "NU_U1") (pintype "passive"))
    )
    (net (code "324") (name "unconnected-(U14-NU-PadU2)") (class "Default")
      (node (ref "U14") (pin "U2") (pinfunction "NU_U2") (pintype "passive"))
    )
    (net (code "325") (name "unconnected-(U14-NU-PadU9)") (class "Default")
      (node (ref "U14") (pin "U9") (pinfunction "NU_U9") (pintype "passive"))
    )
    (net (code "326") (name "unconnected-(U14-NU-PadU10)") (class "Default")
      (node (ref "U14") (pin "U10") (pinfunction "NU_U10") (pintype "passive"))
    )
    (net (code "327") (name "unconnected-(U15-NC-PadB2)") (class "Default")
      (node (ref "U15") (pin "B2") (pinfunction "NC_B2") (pintype "passive"))
    )
    (net (code "328") (name "unconnected-(U15-NC-PadB3)") (class "Default")
      (node (ref "U15") (pin "B3") (pinfunction "NC_B3") (pintype "passive"))
    )
    (net (code "329") (name "unconnected-(U15-NC-PadJ2)") (class "Default")
      (node (ref "U15") (pin "J2") (pinfunction "NC_J2") (pintype "passive"))
    )
    (net (code "330") (name "unconnected-(U15-NC-PadK3)") (class "Default")
      (node (ref "U15") (pin "K3") (pinfunction "NC_K3") (pintype "passive"))
    )
    (net (code "331") (name "unconnected-(U15-NC-PadL3)") (class "Default")
      (node (ref "U15") (pin "L3") (pinfunction "NC_L3") (pintype "passive"))
    )
    (net (code "332") (name "unconnected-(U15-NC-PadR3)") (class "Default")
      (node (ref "U15") (pin "R3") (pinfunction "NC_R3") (pintype "passive"))
    )
    (net (code "333") (name "unconnected-(U15-NC-PadT2)") (class "Default")
      (node (ref "U15") (pin "T2") (pinfunction "NC_T2") (pintype "passive"))
    )
    (net (code "334") (name "unconnected-(U15-NC-PadT3)") (class "Default")
      (node (ref "U15") (pin "T3") (pinfunction "NC_T3") (pintype "passive"))
    )
    (net (code "335") (name "unconnected-(U15-NU-PadA1)") (class "Default")
      (node (ref "U15") (pin "A1") (pinfunction "NU_A1") (pintype "passive"))
    )
    (net (code "336") (name "unconnected-(U15-NU-PadA2)") (class "Default")
      (node (ref "U15") (pin "A2") (pinfunction "NU_A2") (pintype "passive"))
    )
    (net (code "337") (name "unconnected-(U15-NU-PadA9)") (class "Default")
      (node (ref "U15") (pin "A9") (pinfunction "NU_A9") (pintype "passive"))
    )
    (net (code "338") (name "unconnected-(U15-NU-PadA10)") (class "Default")
      (node (ref "U15") (pin "A10") (pinfunction "NU_A10") (pintype "passive"))
    )
    (net (code "339") (name "unconnected-(U15-NU-PadB1)") (class "Default")
      (node (ref "U15") (pin "B1") (pinfunction "NU_B1") (pintype "passive"))
    )
    (net (code "340") (name "unconnected-(U15-NU-PadB10)") (class "Default")
      (node (ref "U15") (pin "B10") (pinfunction "NU_B10") (pintype "passive"))
    )
    (net (code "341") (name "unconnected-(U15-NU-PadT1)") (class "Default")
      (node (ref "U15") (pin "T1") (pinfunction "NU_T1") (pintype "passive"))
    )
    (net (code "342") (name "unconnected-(U15-NU-PadT10)") (class "Default")
      (node (ref "U15") (pin "T10") (pinfunction "NU_T10") (pintype "passive"))
    )
    (net (code "343") (name "unconnected-(U15-NU-PadU1)") (class "Default")
      (node (ref "U15") (pin "U1") (pinfunction "NU_U1") (pintype "passive"))
    )
    (net (code "344") (name "unconnected-(U15-NU-PadU2)") (class "Default")
      (node (ref "U15") (pin "U2") (pinfunction "NU_U2") (pintype "passive"))
    )
    (net (code "345") (name "unconnected-(U15-NU-PadU9)") (class "Default")
      (node (ref "U15") (pin "U9") (pinfunction "NU_U9") (pintype "passive"))
    )
    (net (code "346") (name "unconnected-(U15-NU-PadU10)") (class "Default")
      (node (ref "U15") (pin "U10") (pinfunction "NU_U10") (pintype "passive"))
    )
  )
)
